# guhPLC_V0_1.net
KiCad netlist of a schematic drawn in EAGLE
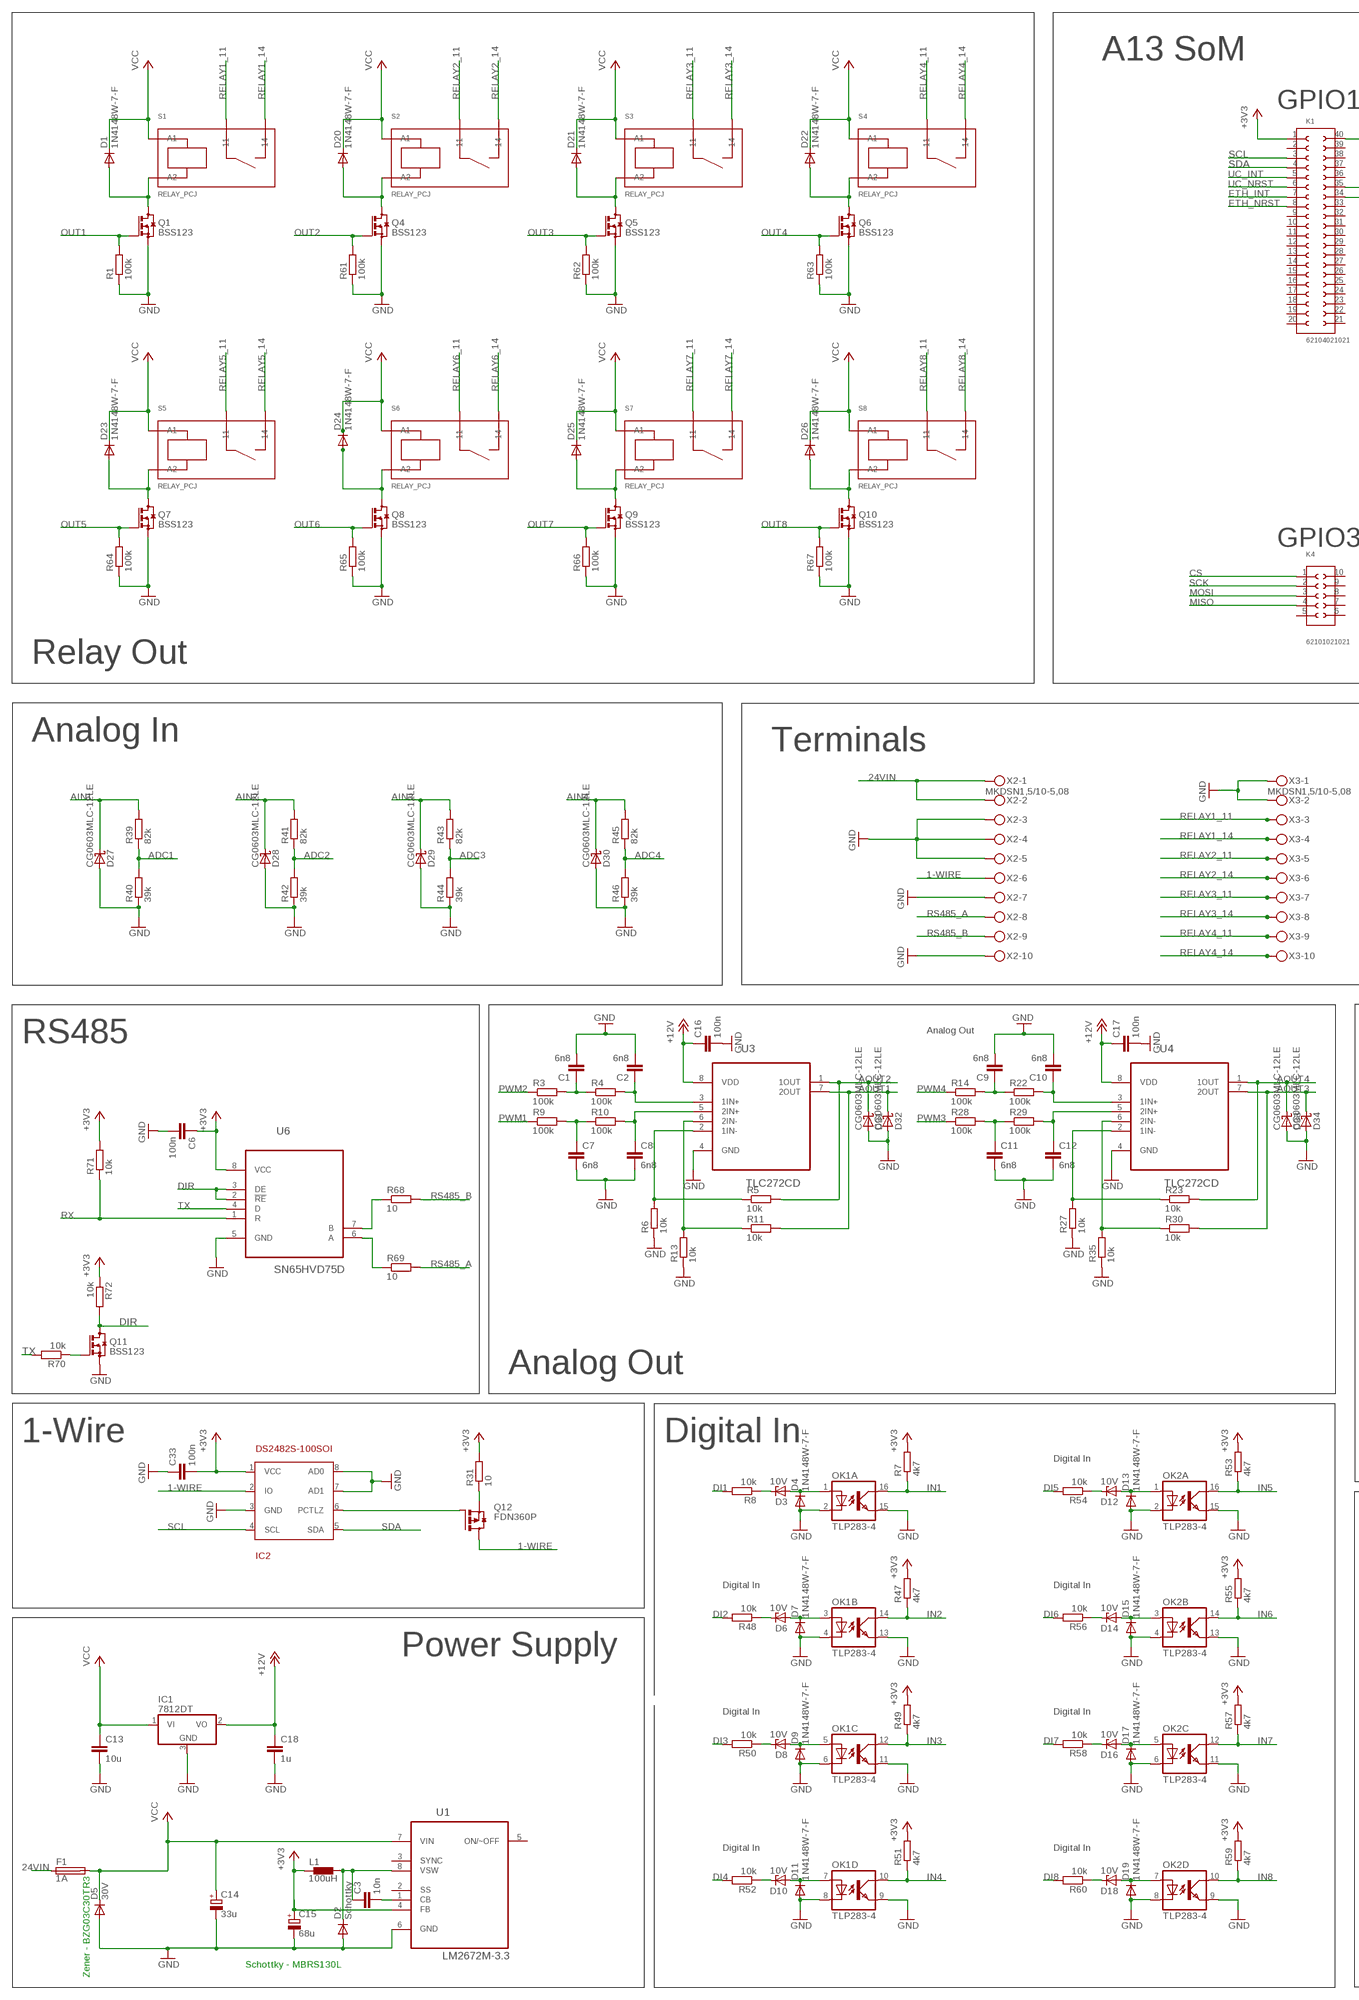
[diagram p0: schematic, sheet 1, part 1 of 2]
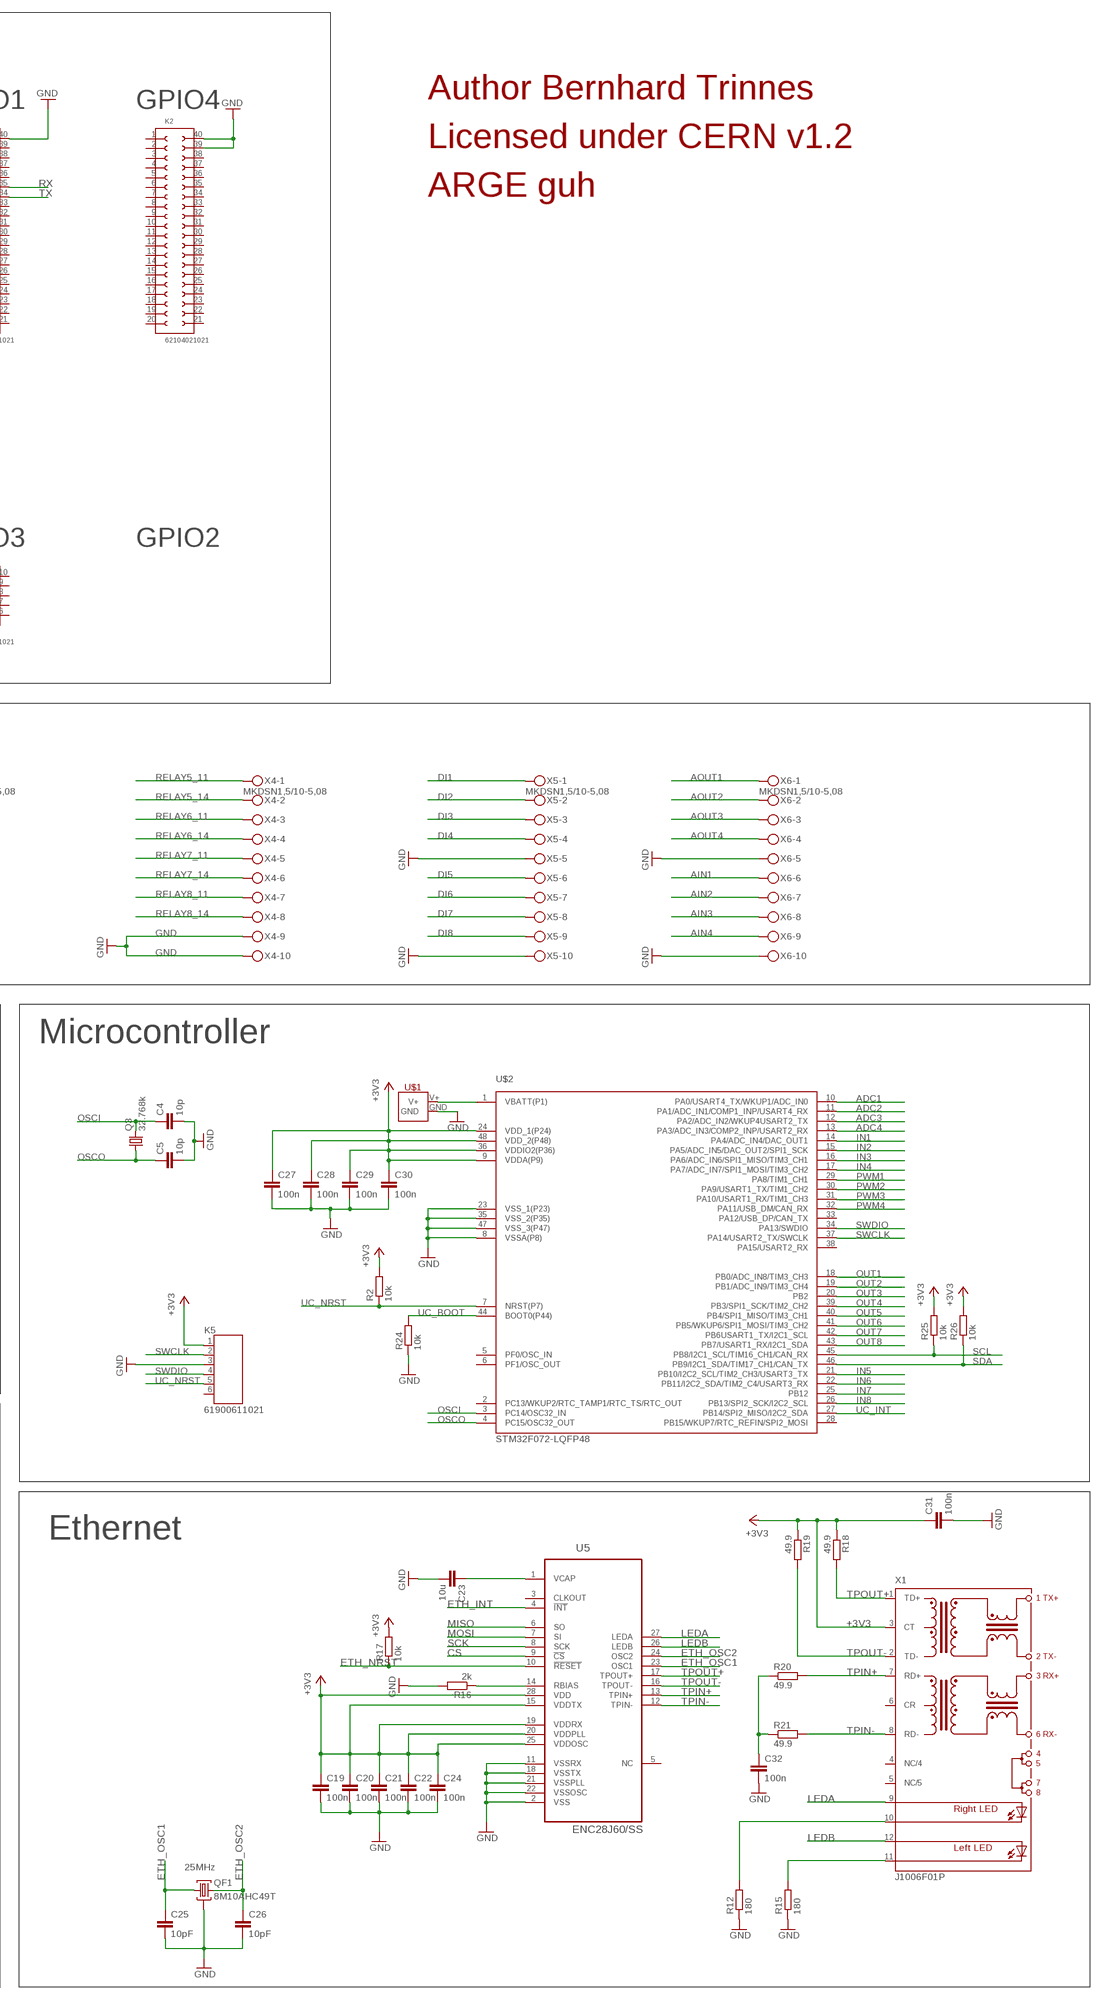
[diagram p1: schematic, sheet 1, part 2 of 2]

(export (version "E")
  (design (tool "Eeschema 10.0.6"))
  (components
    (comp (ref "C1")
      (value "6n8")
      (footprint "eagle-import:C0603")
      (libsource (lib "eagle-import") (part "C-EUC0603"))
    )
    (comp (ref "C2")
      (value "6n8")
      (footprint "eagle-import:C0603")
      (libsource (lib "eagle-import") (part "C-EUC0603"))
    )
    (comp (ref "C3")
      (value "10n")
      (footprint "eagle-import:C0603")
      (libsource (lib "eagle-import") (part "C-EUC0603"))
    )
    (comp (ref "C4")
      (value "10p")
      (footprint "eagle-import:C0603")
      (libsource (lib "eagle-import") (part "C-EUC0603"))
    )
    (comp (ref "C5")
      (value "10p")
      (footprint "eagle-import:C0603")
      (libsource (lib "eagle-import") (part "C-EUC0603"))
    )
    (comp (ref "C6")
      (value "100n")
      (footprint "eagle-import:C0504")
      (libsource (lib "eagle-import") (part "C-EUC0504"))
    )
    (comp (ref "C7")
      (value "6n8")
      (footprint "eagle-import:C0603")
      (libsource (lib "eagle-import") (part "C-EUC0603"))
    )
    (comp (ref "C8")
      (value "6n8")
      (footprint "eagle-import:C0603")
      (libsource (lib "eagle-import") (part "C-EUC0603"))
    )
    (comp (ref "C9")
      (value "6n8")
      (footprint "eagle-import:C0603")
      (libsource (lib "eagle-import") (part "C-EUC0603"))
    )
    (comp (ref "C10")
      (value "6n8")
      (footprint "eagle-import:C0603")
      (libsource (lib "eagle-import") (part "C-EUC0603"))
    )
    (comp (ref "C11")
      (value "6n8")
      (footprint "eagle-import:C0603")
      (libsource (lib "eagle-import") (part "C-EUC0603"))
    )
    (comp (ref "C12")
      (value "6n8")
      (footprint "eagle-import:C0603")
      (libsource (lib "eagle-import") (part "C-EUC0603"))
    )
    (comp (ref "C13")
      (value "10u")
      (footprint "eagle-import:C1206")
      (libsource (lib "eagle-import") (part "C-EUC1206"))
    )
    (comp (ref "C14")
      (value "33u")
      (footprint "eagle-import:CT7343")
      (libsource (lib "eagle-import") (part "CPOL-EUCT7343"))
    )
    (comp (ref "C15")
      (value "68u")
      (footprint "eagle-import:CT6032")
      (libsource (lib "eagle-import") (part "CPOL-EUCT6032"))
    )
    (comp (ref "C16")
      (value "100n")
      (footprint "eagle-import:C0603")
      (libsource (lib "eagle-import") (part "C-EUC0603"))
    )
    (comp (ref "C17")
      (value "100n")
      (footprint "eagle-import:C0603")
      (libsource (lib "eagle-import") (part "C-EUC0603"))
    )
    (comp (ref "C18")
      (value "1u")
      (footprint "eagle-import:C1206")
      (libsource (lib "eagle-import") (part "C-EUC1206"))
    )
    (comp (ref "C19")
      (value "100n")
      (footprint "eagle-import:C0603")
      (libsource (lib "eagle-import") (part "C-EUC0603"))
    )
    (comp (ref "C20")
      (value "100n")
      (footprint "eagle-import:C0603")
      (libsource (lib "eagle-import") (part "C-EUC0603"))
    )
    (comp (ref "C21")
      (value "100n")
      (footprint "eagle-import:C0603")
      (libsource (lib "eagle-import") (part "C-EUC0603"))
    )
    (comp (ref "C22")
      (value "100n")
      (footprint "eagle-import:C0603")
      (libsource (lib "eagle-import") (part "C-EUC0603"))
    )
    (comp (ref "C23")
      (value "10u")
      (footprint "eagle-import:C0603")
      (libsource (lib "eagle-import") (part "C-EUC0603"))
    )
    (comp (ref "C24")
      (value "100n")
      (footprint "eagle-import:C0603")
      (libsource (lib "eagle-import") (part "C-EUC0603"))
    )
    (comp (ref "C25")
      (value "10pF")
      (footprint "eagle-import:C0603")
      (libsource (lib "eagle-import") (part "C-EUC0603"))
    )
    (comp (ref "C26")
      (value "10pF")
      (footprint "eagle-import:C0603")
      (libsource (lib "eagle-import") (part "C-EUC0603"))
    )
    (comp (ref "C27")
      (value "100n")
      (footprint "eagle-import:C0603")
      (libsource (lib "eagle-import") (part "C-EUC0603"))
    )
    (comp (ref "C28")
      (value "100n")
      (footprint "eagle-import:C0603")
      (libsource (lib "eagle-import") (part "C-EUC0603"))
    )
    (comp (ref "C29")
      (value "100n")
      (footprint "eagle-import:C0603")
      (libsource (lib "eagle-import") (part "C-EUC0603"))
    )
    (comp (ref "C30")
      (value "100n")
      (footprint "eagle-import:C0603")
      (libsource (lib "eagle-import") (part "C-EUC0603"))
    )
    (comp (ref "C31")
      (value "100n")
      (footprint "eagle-import:C0603")
      (libsource (lib "eagle-import") (part "C-EUC0603"))
    )
    (comp (ref "C32")
      (value "100n")
      (footprint "eagle-import:C0402")
      (libsource (lib "eagle-import") (part "C-EUC0402"))
    )
    (comp (ref "C33")
      (value "100n")
      (footprint "eagle-import:C0603")
      (libsource (lib "eagle-import") (part "C-EUC0603"))
    )
    (comp (ref "D1")
      (value "1N4148W-7-F")
      (footprint "eagle-import:SOD123")
      (libsource (lib "eagle-import") (part "1N4148W-7-F"))
    )
    (comp (ref "D2")
      (value "Schottky")
      (footprint "eagle-import:DO214AA")
      (libsource (lib "eagle-import") (part "DIODE-DO214AA"))
    )
    (comp (ref "D3")
      (value "10V")
      (footprint "eagle-import:SOD80C")
      (libsource (lib "eagle-import") (part "ZENER-DIODESOD80C"))
    )
    (comp (ref "D4")
      (value "1N4148W-7-F")
      (footprint "eagle-import:SOD123")
      (libsource (lib "eagle-import") (part "1N4148W-7-F"))
    )
    (comp (ref "D5")
      (value "30V")
      (footprint "eagle-import:DO214AC")
      (libsource (lib "eagle-import") (part "DIODE-DO214AC"))
    )
    (comp (ref "D6")
      (value "10V")
      (footprint "eagle-import:SOD80C")
      (libsource (lib "eagle-import") (part "ZENER-DIODESOD80C"))
    )
    (comp (ref "D7")
      (value "1N4148W-7-F")
      (footprint "eagle-import:SOD123")
      (libsource (lib "eagle-import") (part "1N4148W-7-F"))
    )
    (comp (ref "D8")
      (value "10V")
      (footprint "eagle-import:SOD80C")
      (libsource (lib "eagle-import") (part "ZENER-DIODESOD80C"))
    )
    (comp (ref "D9")
      (value "1N4148W-7-F")
      (footprint "eagle-import:SOD123")
      (libsource (lib "eagle-import") (part "1N4148W-7-F"))
    )
    (comp (ref "D10")
      (value "10V")
      (footprint "eagle-import:SOD80C")
      (libsource (lib "eagle-import") (part "ZENER-DIODESOD80C"))
    )
    (comp (ref "D11")
      (value "1N4148W-7-F")
      (footprint "eagle-import:SOD123")
      (libsource (lib "eagle-import") (part "1N4148W-7-F"))
    )
    (comp (ref "D12")
      (value "10V")
      (footprint "eagle-import:SOD80C")
      (libsource (lib "eagle-import") (part "ZENER-DIODESOD80C"))
    )
    (comp (ref "D13")
      (value "1N4148W-7-F")
      (footprint "eagle-import:SOD123")
      (libsource (lib "eagle-import") (part "1N4148W-7-F"))
    )
    (comp (ref "D14")
      (value "10V")
      (footprint "eagle-import:SOD80C")
      (libsource (lib "eagle-import") (part "ZENER-DIODESOD80C"))
    )
    (comp (ref "D15")
      (value "1N4148W-7-F")
      (footprint "eagle-import:SOD123")
      (libsource (lib "eagle-import") (part "1N4148W-7-F"))
    )
    (comp (ref "D16")
      (value "10V")
      (footprint "eagle-import:SOD80C")
      (libsource (lib "eagle-import") (part "ZENER-DIODESOD80C"))
    )
    (comp (ref "D17")
      (value "1N4148W-7-F")
      (footprint "eagle-import:SOD123")
      (libsource (lib "eagle-import") (part "1N4148W-7-F"))
    )
    (comp (ref "D18")
      (value "10V")
      (footprint "eagle-import:SOD80C")
      (libsource (lib "eagle-import") (part "ZENER-DIODESOD80C"))
    )
    (comp (ref "D19")
      (value "1N4148W-7-F")
      (footprint "eagle-import:SOD123")
      (libsource (lib "eagle-import") (part "1N4148W-7-F"))
    )
    (comp (ref "D20")
      (value "1N4148W-7-F")
      (footprint "eagle-import:SOD123")
      (libsource (lib "eagle-import") (part "1N4148W-7-F"))
    )
    (comp (ref "D21")
      (value "1N4148W-7-F")
      (footprint "eagle-import:SOD123")
      (libsource (lib "eagle-import") (part "1N4148W-7-F"))
    )
    (comp (ref "D22")
      (value "1N4148W-7-F")
      (footprint "eagle-import:SOD123")
      (libsource (lib "eagle-import") (part "1N4148W-7-F"))
    )
    (comp (ref "D23")
      (value "1N4148W-7-F")
      (footprint "eagle-import:SOD123")
      (libsource (lib "eagle-import") (part "1N4148W-7-F"))
    )
    (comp (ref "D24")
      (value "1N4148W-7-F")
      (footprint "eagle-import:SOD123")
      (libsource (lib "eagle-import") (part "1N4148W-7-F"))
    )
    (comp (ref "D25")
      (value "1N4148W-7-F")
      (footprint "eagle-import:SOD123")
      (libsource (lib "eagle-import") (part "1N4148W-7-F"))
    )
    (comp (ref "D26")
      (value "1N4148W-7-F")
      (footprint "eagle-import:SOD123")
      (libsource (lib "eagle-import") (part "1N4148W-7-F"))
    )
    (comp (ref "D27")
      (value "CG0603MLC-12LE")
      (footprint "eagle-import:R0603")
      (libsource (lib "eagle-import") (part "CG0603MLC-12LE"))
    )
    (comp (ref "D28")
      (value "CG0603MLC-12LE")
      (footprint "eagle-import:R0603")
      (libsource (lib "eagle-import") (part "CG0603MLC-12LE"))
    )
    (comp (ref "D29")
      (value "CG0603MLC-12LE")
      (footprint "eagle-import:R0603")
      (libsource (lib "eagle-import") (part "CG0603MLC-12LE"))
    )
    (comp (ref "D30")
      (value "CG0603MLC-12LE")
      (footprint "eagle-import:R0603")
      (libsource (lib "eagle-import") (part "CG0603MLC-12LE"))
    )
    (comp (ref "D31")
      (value "CG0603MLC-12LE")
      (footprint "eagle-import:R0603")
      (libsource (lib "eagle-import") (part "CG0603MLC-12LE"))
    )
    (comp (ref "D32")
      (value "CG0603MLC-12LE")
      (footprint "eagle-import:R0603")
      (libsource (lib "eagle-import") (part "CG0603MLC-12LE"))
    )
    (comp (ref "D33")
      (value "CG0603MLC-12LE")
      (footprint "eagle-import:R0603")
      (libsource (lib "eagle-import") (part "CG0603MLC-12LE"))
    )
    (comp (ref "D34")
      (value "CG0603MLC-12LE")
      (footprint "eagle-import:R0603")
      (libsource (lib "eagle-import") (part "CG0603MLC-12LE"))
    )
    (comp (ref "F1")
      (value "1A")
      (footprint "eagle-import:LITTLEFUSE")
      (libsource (lib "eagle-import") (part "LITTLEFUSE"))
    )
    (comp (ref "IC1")
      (value "7812DT")
      (footprint "eagle-import:TO252")
      (libsource (lib "eagle-import") (part "78DT12"))
    )
    (comp (ref "IC2")
      (value "DS2482S-100SOI")
      (footprint "eagle-import:SOIC127P600X175-8N")
      (libsource (lib "eagle-import") (part "DS2482S-100SOI"))
    )
    (comp (ref "K1")
      (value "62104021021")
      (footprint "eagle-import:62104021021")
      (libsource (lib "eagle-import") (part "62104021021"))
    )
    (comp (ref "K2")
      (value "62104021021")
      (footprint "eagle-import:62104021021")
      (libsource (lib "eagle-import") (part "62104021021"))
    )
    (comp (ref "K4")
      (value "62101021021")
      (footprint "eagle-import:62101021021")
      (libsource (lib "eagle-import") (part "62101021021"))
    )
    (comp (ref "K5")
      (value "61900611021")
      (footprint "eagle-import:61900611021")
      (libsource (lib "eagle-import") (part "61900611021"))
    )
    (comp (ref "L1")
      (value "100uH")
      (footprint "eagle-import:DR1030")
      (libsource (lib "eagle-import") (part "DR1030"))
    )
    (comp (ref "OK1")
      (value "TLP283-4")
      (footprint "eagle-import:MINI-FLAT-16")
      (libsource (lib "eagle-import") (part "TLP283-4"))
    )
    (comp (ref "OK2")
      (value "TLP283-4")
      (footprint "eagle-import:MINI-FLAT-16")
      (libsource (lib "eagle-import") (part "TLP283-4"))
    )
    (comp (ref "Q1")
      (value "BSS123")
      (footprint "eagle-import:SOT23")
      (libsource (lib "eagle-import") (part "BSS123"))
    )
    (comp (ref "Q3")
      (value "32.768k")
      (footprint "eagle-import:TC26H")
      (libsource (lib "eagle-import") (part "CRYSTALTC26H"))
    )
    (comp (ref "Q4")
      (value "BSS123")
      (footprint "eagle-import:SOT23")
      (libsource (lib "eagle-import") (part "BSS123"))
    )
    (comp (ref "Q5")
      (value "BSS123")
      (footprint "eagle-import:SOT23")
      (libsource (lib "eagle-import") (part "BSS123"))
    )
    (comp (ref "Q6")
      (value "BSS123")
      (footprint "eagle-import:SOT23")
      (libsource (lib "eagle-import") (part "BSS123"))
    )
    (comp (ref "Q7")
      (value "BSS123")
      (footprint "eagle-import:SOT23")
      (libsource (lib "eagle-import") (part "BSS123"))
    )
    (comp (ref "Q8")
      (value "BSS123")
      (footprint "eagle-import:SOT23")
      (libsource (lib "eagle-import") (part "BSS123"))
    )
    (comp (ref "Q9")
      (value "BSS123")
      (footprint "eagle-import:SOT23")
      (libsource (lib "eagle-import") (part "BSS123"))
    )
    (comp (ref "Q10")
      (value "BSS123")
      (footprint "eagle-import:SOT23")
      (libsource (lib "eagle-import") (part "BSS123"))
    )
    (comp (ref "Q11")
      (value "BSS123")
      (footprint "eagle-import:SOT23")
      (libsource (lib "eagle-import") (part "BSS123"))
    )
    (comp (ref "Q12")
      (value "FDN360P")
      (footprint "eagle-import:SUPER-SOT3")
      (libsource (lib "eagle-import") (part "FDN360P"))
    )
    (comp (ref "QF1")
      (value "8M10AHC49T")
      (footprint "eagle-import:HC49U")
      (libsource (lib "eagle-import") (part "8M10AHC49T"))
    )
    (comp (ref "R1")
      (value "100k")
      (footprint "eagle-import:R0603")
      (libsource (lib "eagle-import") (part "R-EU_R0603"))
    )
    (comp (ref "R2")
      (value "10k")
      (footprint "eagle-import:R0603")
      (libsource (lib "eagle-import") (part "R-EU_R0603"))
    )
    (comp (ref "R3")
      (value "100k")
      (footprint "eagle-import:R0603")
      (libsource (lib "eagle-import") (part "R-EU_R0603"))
    )
    (comp (ref "R4")
      (value "100k")
      (footprint "eagle-import:R0603")
      (libsource (lib "eagle-import") (part "R-EU_R0603"))
    )
    (comp (ref "R5")
      (value "10k")
      (footprint "eagle-import:R0805")
      (libsource (lib "eagle-import") (part "R-EU_R0805"))
    )
    (comp (ref "R6")
      (value "10k")
      (footprint "eagle-import:R0805")
      (libsource (lib "eagle-import") (part "R-EU_R0805"))
    )
    (comp (ref "R7")
      (value "4k7")
      (footprint "eagle-import:R0603")
      (libsource (lib "eagle-import") (part "R-EU_R0603"))
    )
    (comp (ref "R8")
      (value "10k")
      (footprint "eagle-import:R0805")
      (libsource (lib "eagle-import") (part "R-EU_R0805"))
    )
    (comp (ref "R9")
      (value "100k")
      (footprint "eagle-import:R0603")
      (libsource (lib "eagle-import") (part "R-EU_R0603"))
    )
    (comp (ref "R10")
      (value "100k")
      (footprint "eagle-import:R0603")
      (libsource (lib "eagle-import") (part "R-EU_R0603"))
    )
    (comp (ref "R11")
      (value "10k")
      (footprint "eagle-import:R0805")
      (libsource (lib "eagle-import") (part "R-EU_R0805"))
    )
    (comp (ref "R12")
      (value "180")
      (footprint "eagle-import:R0603")
      (libsource (lib "eagle-import") (part "R-EU_R0603"))
    )
    (comp (ref "R13")
      (value "10k")
      (footprint "eagle-import:R0805")
      (libsource (lib "eagle-import") (part "R-EU_R0805"))
    )
    (comp (ref "R14")
      (value "100k")
      (footprint "eagle-import:R0603")
      (libsource (lib "eagle-import") (part "R-EU_R0603"))
    )
    (comp (ref "R15")
      (value "180")
      (footprint "eagle-import:R0603")
      (libsource (lib "eagle-import") (part "R-EU_R0603"))
    )
    (comp (ref "R16")
      (value "2k")
      (footprint "eagle-import:R0603")
      (libsource (lib "eagle-import") (part "R-EU_R0603"))
    )
    (comp (ref "R17")
      (value "10k")
      (footprint "eagle-import:R0603")
      (libsource (lib "eagle-import") (part "R-EU_R0603"))
    )
    (comp (ref "R18")
      (value "49.9")
      (footprint "eagle-import:R0603")
      (libsource (lib "eagle-import") (part "R-EU_R0603"))
    )
    (comp (ref "R19")
      (value "49.9")
      (footprint "eagle-import:R0603")
      (libsource (lib "eagle-import") (part "R-EU_R0603"))
    )
    (comp (ref "R20")
      (value "49.9")
      (footprint "eagle-import:R0603")
      (libsource (lib "eagle-import") (part "R-EU_R0603"))
    )
    (comp (ref "R21")
      (value "49.9")
      (footprint "eagle-import:R0603")
      (libsource (lib "eagle-import") (part "R-EU_R0603"))
    )
    (comp (ref "R22")
      (value "100k")
      (footprint "eagle-import:R0603")
      (libsource (lib "eagle-import") (part "R-EU_R0603"))
    )
    (comp (ref "R23")
      (value "10k")
      (footprint "eagle-import:R0805")
      (libsource (lib "eagle-import") (part "R-EU_R0805"))
    )
    (comp (ref "R24")
      (value "10k")
      (footprint "eagle-import:R0603")
      (libsource (lib "eagle-import") (part "R-EU_R0603"))
    )
    (comp (ref "R25")
      (value "10k")
      (footprint "eagle-import:R0603")
      (libsource (lib "eagle-import") (part "R-EU_R0603"))
    )
    (comp (ref "R26")
      (value "10k")
      (footprint "eagle-import:R0603")
      (libsource (lib "eagle-import") (part "R-EU_R0603"))
    )
    (comp (ref "R27")
      (value "10k")
      (footprint "eagle-import:R0805")
      (libsource (lib "eagle-import") (part "R-EU_R0805"))
    )
    (comp (ref "R28")
      (value "100k")
      (footprint "eagle-import:R0603")
      (libsource (lib "eagle-import") (part "R-EU_R0603"))
    )
    (comp (ref "R29")
      (value "100k")
      (footprint "eagle-import:R0603")
      (libsource (lib "eagle-import") (part "R-EU_R0603"))
    )
    (comp (ref "R30")
      (value "10k")
      (footprint "eagle-import:R0805")
      (libsource (lib "eagle-import") (part "R-EU_R0805"))
    )
    (comp (ref "R31")
      (value "10")
      (footprint "eagle-import:R0805")
      (libsource (lib "eagle-import") (part "R-EU_R0805"))
    )
    (comp (ref "R35")
      (value "10k")
      (footprint "eagle-import:R0805")
      (libsource (lib "eagle-import") (part "R-EU_R0805"))
    )
    (comp (ref "R39")
      (value "82k")
      (footprint "eagle-import:R0805")
      (libsource (lib "eagle-import") (part "R-EU_R0805"))
    )
    (comp (ref "R40")
      (value "39k")
      (footprint "eagle-import:R0805")
      (libsource (lib "eagle-import") (part "R-EU_R0805"))
    )
    (comp (ref "R41")
      (value "82k")
      (footprint "eagle-import:R0805")
      (libsource (lib "eagle-import") (part "R-EU_R0805"))
    )
    (comp (ref "R42")
      (value "39k")
      (footprint "eagle-import:R0805")
      (libsource (lib "eagle-import") (part "R-EU_R0805"))
    )
    (comp (ref "R43")
      (value "82k")
      (footprint "eagle-import:R0805")
      (libsource (lib "eagle-import") (part "R-EU_R0805"))
    )
    (comp (ref "R44")
      (value "39k")
      (footprint "eagle-import:R0805")
      (libsource (lib "eagle-import") (part "R-EU_R0805"))
    )
    (comp (ref "R45")
      (value "82k")
      (footprint "eagle-import:R0805")
      (libsource (lib "eagle-import") (part "R-EU_R0805"))
    )
    (comp (ref "R46")
      (value "39k")
      (footprint "eagle-import:R0805")
      (libsource (lib "eagle-import") (part "R-EU_R0805"))
    )
    (comp (ref "R47")
      (value "4k7")
      (footprint "eagle-import:R0603")
      (libsource (lib "eagle-import") (part "R-EU_R0603"))
    )
    (comp (ref "R48")
      (value "10k")
      (footprint "eagle-import:R0805")
      (libsource (lib "eagle-import") (part "R-EU_R0805"))
    )
    (comp (ref "R49")
      (value "4k7")
      (footprint "eagle-import:R0603")
      (libsource (lib "eagle-import") (part "R-EU_R0603"))
    )
    (comp (ref "R50")
      (value "10k")
      (footprint "eagle-import:R0805")
      (libsource (lib "eagle-import") (part "R-EU_R0805"))
    )
    (comp (ref "R51")
      (value "4k7")
      (footprint "eagle-import:R0603")
      (libsource (lib "eagle-import") (part "R-EU_R0603"))
    )
    (comp (ref "R52")
      (value "10k")
      (footprint "eagle-import:R0805")
      (libsource (lib "eagle-import") (part "R-EU_R0805"))
    )
    (comp (ref "R53")
      (value "4k7")
      (footprint "eagle-import:R0603")
      (libsource (lib "eagle-import") (part "R-EU_R0603"))
    )
    (comp (ref "R54")
      (value "10k")
      (footprint "eagle-import:R0805")
      (libsource (lib "eagle-import") (part "R-EU_R0805"))
    )
    (comp (ref "R55")
      (value "4k7")
      (footprint "eagle-import:R0603")
      (libsource (lib "eagle-import") (part "R-EU_R0603"))
    )
    (comp (ref "R56")
      (value "10k")
      (footprint "eagle-import:R0805")
      (libsource (lib "eagle-import") (part "R-EU_R0805"))
    )
    (comp (ref "R57")
      (value "4k7")
      (footprint "eagle-import:R0603")
      (libsource (lib "eagle-import") (part "R-EU_R0603"))
    )
    (comp (ref "R58")
      (value "10k")
      (footprint "eagle-import:R0805")
      (libsource (lib "eagle-import") (part "R-EU_R0805"))
    )
    (comp (ref "R59")
      (value "4k7")
      (footprint "eagle-import:R0603")
      (libsource (lib "eagle-import") (part "R-EU_R0603"))
    )
    (comp (ref "R60")
      (value "10k")
      (footprint "eagle-import:R0805")
      (libsource (lib "eagle-import") (part "R-EU_R0805"))
    )
    (comp (ref "R61")
      (value "100k")
      (footprint "eagle-import:R0603")
      (libsource (lib "eagle-import") (part "R-EU_R0603"))
    )
    (comp (ref "R62")
      (value "100k")
      (footprint "eagle-import:R0603")
      (libsource (lib "eagle-import") (part "R-EU_R0603"))
    )
    (comp (ref "R63")
      (value "100k")
      (footprint "eagle-import:R0603")
      (libsource (lib "eagle-import") (part "R-EU_R0603"))
    )
    (comp (ref "R64")
      (value "100k")
      (footprint "eagle-import:R0603")
      (libsource (lib "eagle-import") (part "R-EU_R0603"))
    )
    (comp (ref "R65")
      (value "100k")
      (footprint "eagle-import:R0603")
      (libsource (lib "eagle-import") (part "R-EU_R0603"))
    )
    (comp (ref "R66")
      (value "100k")
      (footprint "eagle-import:R0603")
      (libsource (lib "eagle-import") (part "R-EU_R0603"))
    )
    (comp (ref "R67")
      (value "100k")
      (footprint "eagle-import:R0603")
      (libsource (lib "eagle-import") (part "R-EU_R0603"))
    )
    (comp (ref "R68")
      (value "10")
      (footprint "eagle-import:R0603")
      (libsource (lib "eagle-import") (part "R-EU_R0603"))
    )
    (comp (ref "R69")
      (value "10")
      (footprint "eagle-import:R0603")
      (libsource (lib "eagle-import") (part "R-EU_R0603"))
    )
    (comp (ref "R70")
      (value "10k")
      (footprint "eagle-import:R0603")
      (libsource (lib "eagle-import") (part "R-EU_R0603"))
    )
    (comp (ref "R71")
      (value "10k")
      (footprint "eagle-import:R0603")
      (libsource (lib "eagle-import") (part "R-EU_R0603"))
    )
    (comp (ref "R72")
      (value "10k")
      (footprint "eagle-import:R0603")
      (libsource (lib "eagle-import") (part "R-EU_R0603"))
    )
    (comp (ref "S1")
      (value "RELAY_PCJ")
      (footprint "eagle-import:RELAY_PCJ")
      (libsource (lib "eagle-import") (part "RELAY_PCJ"))
    )
    (comp (ref "S2")
      (value "RELAY_PCJ")
      (footprint "eagle-import:RELAY_PCJ")
      (libsource (lib "eagle-import") (part "RELAY_PCJ"))
    )
    (comp (ref "S3")
      (value "RELAY_PCJ")
      (footprint "eagle-import:RELAY_PCJ")
      (libsource (lib "eagle-import") (part "RELAY_PCJ"))
    )
    (comp (ref "S4")
      (value "RELAY_PCJ")
      (footprint "eagle-import:RELAY_PCJ")
      (libsource (lib "eagle-import") (part "RELAY_PCJ"))
    )
    (comp (ref "S5")
      (value "RELAY_PCJ")
      (footprint "eagle-import:RELAY_PCJ")
      (libsource (lib "eagle-import") (part "RELAY_PCJ"))
    )
    (comp (ref "S6")
      (value "RELAY_PCJ")
      (footprint "eagle-import:RELAY_PCJ")
      (libsource (lib "eagle-import") (part "RELAY_PCJ"))
    )
    (comp (ref "S7")
      (value "RELAY_PCJ")
      (footprint "eagle-import:RELAY_PCJ")
      (libsource (lib "eagle-import") (part "RELAY_PCJ"))
    )
    (comp (ref "S8")
      (value "RELAY_PCJ")
      (footprint "eagle-import:RELAY_PCJ")
      (libsource (lib "eagle-import") (part "RELAY_PCJ"))
    )
    (comp (ref "U$1")
      (value "MULTICOMP-CH7410-2032LF")
      (footprint "eagle-import:MULTICOMP-CH7410-2032LF")
      (libsource (lib "eagle-import") (part "MULTICOMP-CH7410-2032LF"))
    )
    (comp (ref "U$2")
      (value "STM32F072-LQFP48")
      (footprint "eagle-import:LQFP48")
      (libsource (lib "eagle-import") (part "STM32F072-LQFP48"))
    )
    (comp (ref "U1")
      (value "LM2672M-3.3")
      (footprint "eagle-import:SOIC127P600X175-8N")
      (libsource (lib "eagle-import") (part "LM2672M-3.3"))
    )
    (comp (ref "U3")
      (value "TLC272CD")
      (footprint "eagle-import:SOIC127P600X175-8N")
      (libsource (lib "eagle-import") (part "TLC272CD"))
    )
    (comp (ref "U4")
      (value "TLC272CD")
      (footprint "eagle-import:SOIC127P600X175-8N")
      (libsource (lib "eagle-import") (part "TLC272CD"))
    )
    (comp (ref "U5")
      (value "ENC28J60/SS")
      (footprint "eagle-import:SOP65P780X200-28N")
      (libsource (lib "eagle-import") (part "ENC28J60/SS"))
    )
    (comp (ref "U6")
      (value "SN65HVD75D")
      (footprint "eagle-import:SOIC127P600X175-8N")
      (libsource (lib "eagle-import") (part "SN65HVD75D"))
    )
    (comp (ref "X1")
      (value "J1006F01P")
      (footprint "eagle-import:J1")
      (libsource (lib "eagle-import") (part "J1006F01P"))
    )
    (comp (ref "X2")
      (value "MKDSN1,5/10-5,08")
      (footprint "eagle-import:MKDSN1,5_10-5,08")
      (fields (field (name "MPN") "SMKDSN1,5/10-5,08"))
      (libsource (lib "eagle-import") (part "MKDSN1,5/10-5,08"))
    )
    (comp (ref "X3")
      (value "MKDSN1,5/10-5,08")
      (footprint "eagle-import:MKDSN1,5_10-5,08")
      (fields (field (name "MPN") "SMKDSN1,5/10-5,08"))
      (libsource (lib "eagle-import") (part "MKDSN1,5/10-5,08"))
    )
    (comp (ref "X4")
      (value "MKDSN1,5/10-5,08")
      (footprint "eagle-import:MKDSN1,5_10-5,08")
      (fields (field (name "MPN") "SMKDSN1,5/10-5,08"))
      (libsource (lib "eagle-import") (part "MKDSN1,5/10-5,08"))
    )
    (comp (ref "X5")
      (value "MKDSN1,5/10-5,08")
      (footprint "eagle-import:MKDSN1,5_10-5,08")
      (fields (field (name "MPN") "SMKDSN1,5/10-5,08"))
      (libsource (lib "eagle-import") (part "MKDSN1,5/10-5,08"))
    )
    (comp (ref "X6")
      (value "MKDSN1,5/10-5,08")
      (footprint "eagle-import:MKDSN1,5_10-5,08")
      (fields (field (name "MPN") "SMKDSN1,5/10-5,08"))
      (libsource (lib "eagle-import") (part "MKDSN1,5/10-5,08"))
    )
  )
  (nets
    (net (code "1") (name "+3V3") (class "Default")
      (node (ref "C15") (pin "+") (pinfunction "+_+") (pintype "passive"))
      (node (ref "C19") (pin "1") (pinfunction "1_1") (pintype "passive"))
      (node (ref "C20") (pin "1") (pinfunction "1_1") (pintype "passive"))
      (node (ref "C21") (pin "1") (pinfunction "1_1") (pintype "passive"))
      (node (ref "C22") (pin "1") (pinfunction "1_1") (pintype "passive"))
      (node (ref "C24") (pin "1") (pinfunction "1_1") (pintype "passive"))
      (node (ref "C27") (pin "1") (pinfunction "1_1") (pintype "passive"))
      (node (ref "C28") (pin "1") (pinfunction "1_1") (pintype "passive"))
      (node (ref "C29") (pin "1") (pinfunction "1_1") (pintype "passive"))
      (node (ref "C30") (pin "1") (pinfunction "1_1") (pintype "passive"))
      (node (ref "C31") (pin "1") (pinfunction "1_1") (pintype "passive"))
      (node (ref "C33") (pin "2") (pinfunction "2_2") (pintype "passive"))
      (node (ref "C6") (pin "1") (pinfunction "1_1") (pintype "passive"))
      (node (ref "IC2") (pin "1") (pinfunction "VCC_1") (pintype "power_in"))
      (node (ref "K1") (pin "1") (pinfunction "1_1") (pintype "passive"))
      (node (ref "K5") (pin "1") (pinfunction "1_1") (pintype "passive"))
      (node (ref "L1") (pin "1") (pinfunction "1_1") (pintype "passive"))
      (node (ref "R17") (pin "2") (pinfunction "2_2") (pintype "passive"))
      (node (ref "R18") (pin "1") (pinfunction "1_1") (pintype "passive"))
      (node (ref "R19") (pin "1") (pinfunction "1_1") (pintype "passive"))
      (node (ref "R2") (pin "2") (pinfunction "2_2") (pintype "passive"))
      (node (ref "R25") (pin "2") (pinfunction "2_2") (pintype "passive"))
      (node (ref "R26") (pin "2") (pinfunction "2_2") (pintype "passive"))
      (node (ref "R31") (pin "2") (pinfunction "2_2") (pintype "passive"))
      (node (ref "R47") (pin "2") (pinfunction "2_2") (pintype "passive"))
      (node (ref "R49") (pin "2") (pinfunction "2_2") (pintype "passive"))
      (node (ref "R51") (pin "2") (pinfunction "2_2") (pintype "passive"))
      (node (ref "R53") (pin "2") (pinfunction "2_2") (pintype "passive"))
      (node (ref "R55") (pin "2") (pinfunction "2_2") (pintype "passive"))
      (node (ref "R57") (pin "2") (pinfunction "2_2") (pintype "passive"))
      (node (ref "R59") (pin "2") (pinfunction "2_2") (pintype "passive"))
      (node (ref "R7") (pin "2") (pinfunction "2_2") (pintype "passive"))
      (node (ref "R71") (pin "2") (pinfunction "2_2") (pintype "passive"))
      (node (ref "R72") (pin "1") (pinfunction "1_1") (pintype "passive"))
      (node (ref "U$2") (pin "24") (pinfunction "VDD_1(P24)_24") (pintype "bidirectional"))
      (node (ref "U$2") (pin "36") (pinfunction "VDDIO2(P36)_36") (pintype "bidirectional"))
      (node (ref "U$2") (pin "48") (pinfunction "VDD_2(P48)_48") (pintype "bidirectional"))
      (node (ref "U$2") (pin "9") (pinfunction "VDDA(P9)_9") (pintype "bidirectional"))
      (node (ref "U1") (pin "4") (pinfunction "FB_4") (pintype "input"))
      (node (ref "U5") (pin "15") (pinfunction "VDDTX_15") (pintype "power_in"))
      (node (ref "U5") (pin "19") (pinfunction "VDDRX_19") (pintype "power_in"))
      (node (ref "U5") (pin "20") (pinfunction "VDDPLL_20") (pintype "power_in"))
      (node (ref "U5") (pin "25") (pinfunction "VDDOSC_25") (pintype "power_in"))
      (node (ref "U5") (pin "28") (pinfunction "VDD_28") (pintype "power_in"))
      (node (ref "U6") (pin "8") (pinfunction "VCC_8") (pintype "power_in"))
      (node (ref "X1") (pin "3") (pinfunction "CT_3") (pintype "input"))
    )
    (net (code "2") (name "+12V") (class "Default")
      (node (ref "C16") (pin "1") (pinfunction "1_1") (pintype "passive"))
      (node (ref "C17") (pin "1") (pinfunction "1_1") (pintype "passive"))
      (node (ref "C18") (pin "1") (pinfunction "1_1") (pintype "passive"))
      (node (ref "IC1") (pin "2") (pinfunction "VO_2") (pintype "passive"))
      (node (ref "U3") (pin "8") (pinfunction "VDD_8") (pintype "power_in"))
      (node (ref "U4") (pin "8") (pinfunction "VDD_8") (pintype "power_in"))
    )
    (net (code "3") (name "/1-WIRE") (class "Default")
      (node (ref "IC2") (pin "2") (pinfunction "IO_2") (pintype "bidirectional"))
      (node (ref "Q12") (pin "3") (pinfunction "D_3") (pintype "passive"))
      (node (ref "X2") (pin "6") (pinfunction "KL_6") (pintype "passive"))
    )
    (net (code "4") (name "/24VIN") (class "Default")
      (node (ref "F1") (pin "1") (pinfunction "1_1") (pintype "passive"))
      (node (ref "X2") (pin "1") (pinfunction "KL_1") (pintype "passive"))
      (node (ref "X2") (pin "2") (pinfunction "KL_2") (pintype "passive"))
    )
    (net (code "5") (name "/ADC1") (class "Default")
      (node (ref "R39") (pin "1") (pinfunction "1_1") (pintype "passive"))
      (node (ref "R40") (pin "2") (pinfunction "2_2") (pintype "passive"))
      (node (ref "U$2") (pin "10") (pinfunction "PA0/USART4_TX/WKUP1/ADC_IN0_10") (pintype "bidirectional"))
    )
    (net (code "6") (name "/ADC2") (class "Default")
      (node (ref "R41") (pin "1") (pinfunction "1_1") (pintype "passive"))
      (node (ref "R42") (pin "2") (pinfunction "2_2") (pintype "passive"))
      (node (ref "U$2") (pin "11") (pinfunction "PA1/ADC_IN1/COMP1_INP/USART4_RX_11") (pintype "bidirectional"))
    )
    (net (code "7") (name "/ADC3") (class "Default")
      (node (ref "R43") (pin "1") (pinfunction "1_1") (pintype "passive"))
      (node (ref "R44") (pin "2") (pinfunction "2_2") (pintype "passive"))
      (node (ref "U$2") (pin "12") (pinfunction "PA2/ADC_IN2/WKUP4USART2_TX_12") (pintype "bidirectional"))
    )
    (net (code "8") (name "/ADC4") (class "Default")
      (node (ref "R45") (pin "1") (pinfunction "1_1") (pintype "passive"))
      (node (ref "R46") (pin "2") (pinfunction "2_2") (pintype "passive"))
      (node (ref "U$2") (pin "13") (pinfunction "PA3/ADC_IN3/COMP2_INP/USART2_RX_13") (pintype "bidirectional"))
    )
    (net (code "9") (name "/AIN1") (class "Default")
      (node (ref "D27") (pin "2") (pinfunction "C_2") (pintype "passive"))
      (node (ref "R39") (pin "2") (pinfunction "2_2") (pintype "passive"))
      (node (ref "X6") (pin "6") (pinfunction "KL_6") (pintype "passive"))
    )
    (net (code "10") (name "/AIN2") (class "Default")
      (node (ref "D28") (pin "2") (pinfunction "C_2") (pintype "passive"))
      (node (ref "R41") (pin "2") (pinfunction "2_2") (pintype "passive"))
      (node (ref "X6") (pin "7") (pinfunction "KL_7") (pintype "passive"))
    )
    (net (code "11") (name "/AIN3") (class "Default")
      (node (ref "D29") (pin "2") (pinfunction "C_2") (pintype "passive"))
      (node (ref "R43") (pin "2") (pinfunction "2_2") (pintype "passive"))
      (node (ref "X6") (pin "8") (pinfunction "KL_8") (pintype "passive"))
    )
    (net (code "12") (name "/AIN4") (class "Default")
      (node (ref "D30") (pin "2") (pinfunction "C_2") (pintype "passive"))
      (node (ref "R45") (pin "2") (pinfunction "2_2") (pintype "passive"))
      (node (ref "X6") (pin "9") (pinfunction "KL_9") (pintype "passive"))
    )
    (net (code "13") (name "/AOUT1") (class "Default")
      (node (ref "D32") (pin "2") (pinfunction "C_2") (pintype "passive"))
      (node (ref "R11") (pin "2") (pinfunction "2_2") (pintype "passive"))
      (node (ref "U3") (pin "7") (pinfunction "2OUT_7") (pintype "output"))
      (node (ref "X6") (pin "1") (pinfunction "KL_1") (pintype "passive"))
    )
    (net (code "14") (name "/AOUT2") (class "Default")
      (node (ref "D31") (pin "2") (pinfunction "C_2") (pintype "passive"))
      (node (ref "R5") (pin "2") (pinfunction "2_2") (pintype "passive"))
      (node (ref "U3") (pin "1") (pinfunction "1OUT_1") (pintype "output"))
      (node (ref "X6") (pin "2") (pinfunction "KL_2") (pintype "passive"))
    )
    (net (code "15") (name "/AOUT3") (class "Default")
      (node (ref "D34") (pin "2") (pinfunction "C_2") (pintype "passive"))
      (node (ref "R30") (pin "2") (pinfunction "2_2") (pintype "passive"))
      (node (ref "U4") (pin "7") (pinfunction "2OUT_7") (pintype "output"))
      (node (ref "X6") (pin "3") (pinfunction "KL_3") (pintype "passive"))
    )
    (net (code "16") (name "/AOUT4") (class "Default")
      (node (ref "D33") (pin "2") (pinfunction "C_2") (pintype "passive"))
      (node (ref "R23") (pin "2") (pinfunction "2_2") (pintype "passive"))
      (node (ref "U4") (pin "1") (pinfunction "1OUT_1") (pintype "output"))
      (node (ref "X6") (pin "4") (pinfunction "KL_4") (pintype "passive"))
    )
    (net (code "17") (name "/CS") (class "Default")
      (node (ref "K4") (pin "1") (pinfunction "1_1") (pintype "passive"))
      (node (ref "U5") (pin "9") (pinfunction "~{CS}_9") (pintype "passive"))
    )
    (net (code "18") (name "/DI1") (class "Default")
      (node (ref "R8") (pin "2") (pinfunction "2_2") (pintype "passive"))
      (node (ref "X5") (pin "1") (pinfunction "KL_1") (pintype "passive"))
    )
    (net (code "19") (name "/DI2") (class "Default")
      (node (ref "R48") (pin "2") (pinfunction "2_2") (pintype "passive"))
      (node (ref "X5") (pin "2") (pinfunction "KL_2") (pintype "passive"))
    )
    (net (code "20") (name "/DI3") (class "Default")
      (node (ref "R50") (pin "2") (pinfunction "2_2") (pintype "passive"))
      (node (ref "X5") (pin "3") (pinfunction "KL_3") (pintype "passive"))
    )
    (net (code "21") (name "/DI4") (class "Default")
      (node (ref "R52") (pin "2") (pinfunction "2_2") (pintype "passive"))
      (node (ref "X5") (pin "4") (pinfunction "KL_4") (pintype "passive"))
    )
    (net (code "22") (name "/DI5") (class "Default")
      (node (ref "R54") (pin "2") (pinfunction "2_2") (pintype "passive"))
      (node (ref "X5") (pin "6") (pinfunction "KL_6") (pintype "passive"))
    )
    (net (code "23") (name "/DI6") (class "Default")
      (node (ref "R56") (pin "2") (pinfunction "2_2") (pintype "passive"))
      (node (ref "X5") (pin "7") (pinfunction "KL_7") (pintype "passive"))
    )
    (net (code "24") (name "/DI7") (class "Default")
      (node (ref "R58") (pin "2") (pinfunction "2_2") (pintype "passive"))
      (node (ref "X5") (pin "8") (pinfunction "KL_8") (pintype "passive"))
    )
    (net (code "25") (name "/DI8") (class "Default")
      (node (ref "R60") (pin "2") (pinfunction "2_2") (pintype "passive"))
      (node (ref "X5") (pin "9") (pinfunction "KL_9") (pintype "passive"))
    )
    (net (code "26") (name "/DIR") (class "Default")
      (node (ref "Q11") (pin "3") (pinfunction "D_3") (pintype "passive"))
      (node (ref "R72") (pin "2") (pinfunction "2_2") (pintype "passive"))
      (node (ref "U6") (pin "2") (pinfunction "~{RE}_2") (pintype "input"))
      (node (ref "U6") (pin "3") (pinfunction "DE_3") (pintype "input"))
    )
    (net (code "27") (name "/ETH_INT") (class "Default")
      (node (ref "K1") (pin "7") (pinfunction "7_7") (pintype "passive"))
      (node (ref "U5") (pin "4") (pinfunction "~{INT}_4") (pintype "passive"))
    )
    (net (code "28") (name "/ETH_NRST") (class "Default")
      (node (ref "K1") (pin "8") (pinfunction "8_8") (pintype "passive"))
      (node (ref "R17") (pin "1") (pinfunction "1_1") (pintype "passive"))
      (node (ref "U5") (pin "10") (pinfunction "~{RESET}_10") (pintype "passive"))
    )
    (net (code "29") (name "/ETH_OSC1") (class "Default")
      (node (ref "C25") (pin "1") (pinfunction "1_1") (pintype "passive"))
      (node (ref "QF1") (pin "1") (pinfunction "1_1") (pintype "passive"))
      (node (ref "U5") (pin "23") (pinfunction "OSC1_23") (pintype "passive"))
    )
    (net (code "30") (name "/ETH_OSC2") (class "Default")
      (node (ref "C26") (pin "1") (pinfunction "1_1") (pintype "passive"))
      (node (ref "QF1") (pin "3") (pinfunction "3_3") (pintype "passive"))
      (node (ref "U5") (pin "24") (pinfunction "OSC2_24") (pintype "passive"))
    )
    (net (code "31") (name "/IN1") (class "Default")
      (node (ref "OK1") (pin "16") (pinfunction "COL_16") (pintype "passive"))
      (node (ref "R7") (pin "1") (pinfunction "1_1") (pintype "passive"))
      (node (ref "U$2") (pin "14") (pinfunction "PA4/ADC_IN4/DAC_OUT1_14") (pintype "bidirectional"))
    )
    (net (code "32") (name "/IN2") (class "Default")
      (node (ref "OK1") (pin "14") (pinfunction "COL_14") (pintype "passive"))
      (node (ref "R47") (pin "1") (pinfunction "1_1") (pintype "passive"))
      (node (ref "U$2") (pin "15") (pinfunction "PA5/ADC_IN5/DAC_OUT2/SPI1_SCK_15") (pintype "bidirectional"))
    )
    (net (code "33") (name "/IN3") (class "Default")
      (node (ref "OK1") (pin "12") (pinfunction "COL_12") (pintype "passive"))
      (node (ref "R49") (pin "1") (pinfunction "1_1") (pintype "passive"))
      (node (ref "U$2") (pin "16") (pinfunction "PA6/ADC_IN6/SPI1_MISO/TIM3_CH1_16") (pintype "bidirectional"))
    )
    (net (code "34") (name "/IN4") (class "Default")
      (node (ref "OK1") (pin "10") (pinfunction "COL_10") (pintype "passive"))
      (node (ref "R51") (pin "1") (pinfunction "1_1") (pintype "passive"))
      (node (ref "U$2") (pin "17") (pinfunction "PA7/ADC_IN7/SPI1_MOSI/TIM3_CH2_17") (pintype "bidirectional"))
    )
    (net (code "35") (name "/IN5") (class "Default")
      (node (ref "OK2") (pin "16") (pinfunction "COL_16") (pintype "passive"))
      (node (ref "R53") (pin "1") (pinfunction "1_1") (pintype "passive"))
      (node (ref "U$2") (pin "21") (pinfunction "PB10/I2C2_SCL/TIM2_CH3/USART3_TX_21") (pintype "bidirectional"))
    )
    (net (code "36") (name "/IN6") (class "Default")
      (node (ref "OK2") (pin "14") (pinfunction "COL_14") (pintype "passive"))
      (node (ref "R55") (pin "1") (pinfunction "1_1") (pintype "passive"))
      (node (ref "U$2") (pin "22") (pinfunction "PB11/I2C2_SDA/TIM2_C4/USART3_RX_22") (pintype "bidirectional"))
    )
    (net (code "37") (name "/IN7") (class "Default")
      (node (ref "OK2") (pin "12") (pinfunction "COL_12") (pintype "passive"))
      (node (ref "R57") (pin "1") (pinfunction "1_1") (pintype "passive"))
      (node (ref "U$2") (pin "25") (pinfunction "PB12_25") (pintype "bidirectional"))
    )
    (net (code "38") (name "/IN8") (class "Default")
      (node (ref "OK2") (pin "10") (pinfunction "COL_10") (pintype "passive"))
      (node (ref "R59") (pin "1") (pinfunction "1_1") (pintype "passive"))
      (node (ref "U$2") (pin "26") (pinfunction "PB13/SPI2_SCK/I2C2_SCL_26") (pintype "bidirectional"))
    )
    (net (code "39") (name "/LEDA") (class "Default")
      (node (ref "U5") (pin "27") (pinfunction "LEDA_27") (pintype "passive"))
      (node (ref "X1") (pin "9") (pinfunction "A-R_9") (pintype "passive"))
    )
    (net (code "40") (name "/LEDB") (class "Default")
      (node (ref "U5") (pin "26") (pinfunction "LEDB_26") (pintype "passive"))
      (node (ref "X1") (pin "12") (pinfunction "A-L_12") (pintype "passive"))
    )
    (net (code "41") (name "/MISO") (class "Default")
      (node (ref "K4") (pin "4") (pinfunction "4_4") (pintype "passive"))
      (node (ref "U5") (pin "6") (pinfunction "SO_6") (pintype "passive"))
    )
    (net (code "42") (name "/MOSI") (class "Default")
      (node (ref "K4") (pin "3") (pinfunction "3_3") (pintype "passive"))
      (node (ref "U5") (pin "7") (pinfunction "SI_7") (pintype "passive"))
    )
    (net (code "43") (name "/OSCI") (class "Default")
      (node (ref "C4") (pin "1") (pinfunction "1_1") (pintype "passive"))
      (node (ref "Q3") (pin "2") (pinfunction "2_2") (pintype "passive"))
      (node (ref "U$2") (pin "3") (pinfunction "PC14/OSC32_IN_3") (pintype "bidirectional"))
    )
    (net (code "44") (name "/OSCO") (class "Default")
      (node (ref "C5") (pin "1") (pinfunction "1_1") (pintype "passive"))
      (node (ref "Q3") (pin "1") (pinfunction "1_1") (pintype "passive"))
      (node (ref "U$2") (pin "4") (pinfunction "PC15/OSC32_OUT_4") (pintype "bidirectional"))
    )
    (net (code "45") (name "/OUT1") (class "Default")
      (node (ref "Q1") (pin "1") (pinfunction "G_1") (pintype "passive"))
      (node (ref "R1") (pin "2") (pinfunction "2_2") (pintype "passive"))
      (node (ref "U$2") (pin "18") (pinfunction "PB0/ADC_IN8/TIM3_CH3_18") (pintype "bidirectional"))
    )
    (net (code "46") (name "/OUT2") (class "Default")
      (node (ref "Q4") (pin "1") (pinfunction "G_1") (pintype "passive"))
      (node (ref "R61") (pin "2") (pinfunction "2_2") (pintype "passive"))
      (node (ref "U$2") (pin "19") (pinfunction "PB1/ADC_IN9/TIM3_CH4_19") (pintype "bidirectional"))
    )
    (net (code "47") (name "/OUT3") (class "Default")
      (node (ref "Q5") (pin "1") (pinfunction "G_1") (pintype "passive"))
      (node (ref "R62") (pin "2") (pinfunction "2_2") (pintype "passive"))
      (node (ref "U$2") (pin "20") (pinfunction "PB2_20") (pintype "bidirectional"))
    )
    (net (code "48") (name "/OUT4") (class "Default")
      (node (ref "Q6") (pin "1") (pinfunction "G_1") (pintype "passive"))
      (node (ref "R63") (pin "2") (pinfunction "2_2") (pintype "passive"))
      (node (ref "U$2") (pin "39") (pinfunction "PB3/SPI1_SCK/TIM2_CH2_39") (pintype "bidirectional"))
    )
    (net (code "49") (name "/OUT5") (class "Default")
      (node (ref "Q7") (pin "1") (pinfunction "G_1") (pintype "passive"))
      (node (ref "R64") (pin "2") (pinfunction "2_2") (pintype "passive"))
      (node (ref "U$2") (pin "40") (pinfunction "PB4/SPI1_MISO/TIM3_CH1_40") (pintype "bidirectional"))
    )
    (net (code "50") (name "/OUT6") (class "Default")
      (node (ref "Q8") (pin "1") (pinfunction "G_1") (pintype "passive"))
      (node (ref "R65") (pin "2") (pinfunction "2_2") (pintype "passive"))
      (node (ref "U$2") (pin "41") (pinfunction "PB5/WKUP6/SPI1_MOSI/TIM3_CH2_41") (pintype "bidirectional"))
    )
    (net (code "51") (name "/OUT7") (class "Default")
      (node (ref "Q9") (pin "1") (pinfunction "G_1") (pintype "passive"))
      (node (ref "R66") (pin "2") (pinfunction "2_2") (pintype "passive"))
      (node (ref "U$2") (pin "42") (pinfunction "PB6USART1_TX/I2C1_SCL_42") (pintype "bidirectional"))
    )
    (net (code "52") (name "/OUT8") (class "Default")
      (node (ref "Q10") (pin "1") (pinfunction "G_1") (pintype "passive"))
      (node (ref "R67") (pin "2") (pinfunction "2_2") (pintype "passive"))
      (node (ref "U$2") (pin "43") (pinfunction "PB7/USART1_RX/I2C1_SDA_43") (pintype "bidirectional"))
    )
    (net (code "53") (name "/PWM1") (class "Default")
      (node (ref "R9") (pin "1") (pinfunction "1_1") (pintype "passive"))
      (node (ref "U$2") (pin "29") (pinfunction "PA8/TIM1_CH1_29") (pintype "bidirectional"))
    )
    (net (code "54") (name "/PWM2") (class "Default")
      (node (ref "R3") (pin "1") (pinfunction "1_1") (pintype "passive"))
      (node (ref "U$2") (pin "30") (pinfunction "PA9/USART1_TX/TIM1_CH2_30") (pintype "bidirectional"))
    )
    (net (code "55") (name "/PWM3") (class "Default")
      (node (ref "R28") (pin "1") (pinfunction "1_1") (pintype "passive"))
      (node (ref "U$2") (pin "31") (pinfunction "PA10/USART1_RX/TIM1_CH3_31") (pintype "bidirectional"))
    )
    (net (code "56") (name "/PWM4") (class "Default")
      (node (ref "R14") (pin "1") (pinfunction "1_1") (pintype "passive"))
      (node (ref "U$2") (pin "32") (pinfunction "PA11/USB_DM/CAN_RX_32") (pintype "bidirectional"))
    )
    (net (code "57") (name "/RELAY1_11") (class "Default")
      (node (ref "S1") (pin "11") (pinfunction "11_11") (pintype "bidirectional"))
      (node (ref "X3") (pin "3") (pinfunction "KL_3") (pintype "passive"))
    )
    (net (code "58") (name "/RELAY1_14") (class "Default")
      (node (ref "S1") (pin "14") (pinfunction "14_14") (pintype "bidirectional"))
      (node (ref "X3") (pin "4") (pinfunction "KL_4") (pintype "passive"))
    )
    (net (code "59") (name "/RELAY2_11") (class "Default")
      (node (ref "S2") (pin "11") (pinfunction "11_11") (pintype "bidirectional"))
      (node (ref "X3") (pin "5") (pinfunction "KL_5") (pintype "passive"))
    )
    (net (code "60") (name "/RELAY2_14") (class "Default")
      (node (ref "S2") (pin "14") (pinfunction "14_14") (pintype "bidirectional"))
      (node (ref "X3") (pin "6") (pinfunction "KL_6") (pintype "passive"))
    )
    (net (code "61") (name "/RELAY3_11") (class "Default")
      (node (ref "S3") (pin "11") (pinfunction "11_11") (pintype "bidirectional"))
      (node (ref "X3") (pin "7") (pinfunction "KL_7") (pintype "passive"))
    )
    (net (code "62") (name "/RELAY3_14") (class "Default")
      (node (ref "S3") (pin "14") (pinfunction "14_14") (pintype "bidirectional"))
      (node (ref "X3") (pin "8") (pinfunction "KL_8") (pintype "passive"))
    )
    (net (code "63") (name "/RELAY4_11") (class "Default")
      (node (ref "S4") (pin "11") (pinfunction "11_11") (pintype "bidirectional"))
      (node (ref "X3") (pin "9") (pinfunction "KL_9") (pintype "passive"))
    )
    (net (code "64") (name "/RELAY4_14") (class "Default")
      (node (ref "S4") (pin "14") (pinfunction "14_14") (pintype "bidirectional"))
      (node (ref "X3") (pin "10") (pinfunction "KL_10") (pintype "passive"))
    )
    (net (code "65") (name "/RELAY5_11") (class "Default")
      (node (ref "S5") (pin "11") (pinfunction "11_11") (pintype "bidirectional"))
      (node (ref "X4") (pin "1") (pinfunction "KL_1") (pintype "passive"))
    )
    (net (code "66") (name "/RELAY5_14") (class "Default")
      (node (ref "S5") (pin "14") (pinfunction "14_14") (pintype "bidirectional"))
      (node (ref "X4") (pin "2") (pinfunction "KL_2") (pintype "passive"))
    )
    (net (code "67") (name "/RELAY6_11") (class "Default")
      (node (ref "S6") (pin "11") (pinfunction "11_11") (pintype "bidirectional"))
      (node (ref "X4") (pin "3") (pinfunction "KL_3") (pintype "passive"))
    )
    (net (code "68") (name "/RELAY6_14") (class "Default")
      (node (ref "S6") (pin "14") (pinfunction "14_14") (pintype "bidirectional"))
      (node (ref "X4") (pin "4") (pinfunction "KL_4") (pintype "passive"))
    )
    (net (code "69") (name "/RELAY7_11") (class "Default")
      (node (ref "S7") (pin "11") (pinfunction "11_11") (pintype "bidirectional"))
      (node (ref "X4") (pin "5") (pinfunction "KL_5") (pintype "passive"))
    )
    (net (code "70") (name "/RELAY7_14") (class "Default")
      (node (ref "S7") (pin "14") (pinfunction "14_14") (pintype "bidirectional"))
      (node (ref "X4") (pin "6") (pinfunction "KL_6") (pintype "passive"))
    )
    (net (code "71") (name "/RELAY8_11") (class "Default")
      (node (ref "S8") (pin "11") (pinfunction "11_11") (pintype "bidirectional"))
      (node (ref "X4") (pin "7") (pinfunction "KL_7") (pintype "passive"))
    )
    (net (code "72") (name "/RELAY8_14") (class "Default")
      (node (ref "S8") (pin "14") (pinfunction "14_14") (pintype "bidirectional"))
      (node (ref "X4") (pin "8") (pinfunction "KL_8") (pintype "passive"))
    )
    (net (code "73") (name "/RS485_A") (class "Default")
      (node (ref "R69") (pin "2") (pinfunction "2_2") (pintype "passive"))
      (node (ref "X2") (pin "8") (pinfunction "KL_8") (pintype "passive"))
    )
    (net (code "74") (name "/RS485_B") (class "Default")
      (node (ref "R68") (pin "2") (pinfunction "2_2") (pintype "passive"))
      (node (ref "X2") (pin "9") (pinfunction "KL_9") (pintype "passive"))
    )
    (net (code "75") (name "/RX") (class "Default")
      (node (ref "K1") (pin "35") (pinfunction "35_35") (pintype "passive"))
      (node (ref "R71") (pin "1") (pinfunction "1_1") (pintype "passive"))
      (node (ref "U6") (pin "1") (pinfunction "R_1") (pintype "input"))
    )
    (net (code "76") (name "/SCK") (class "Default")
      (node (ref "K4") (pin "2") (pinfunction "2_2") (pintype "passive"))
      (node (ref "U5") (pin "8") (pinfunction "SCK_8") (pintype "passive"))
    )
    (net (code "77") (name "/SCL") (class "Default")
      (node (ref "IC2") (pin "4") (pinfunction "SCL_4") (pintype "bidirectional"))
      (node (ref "K1") (pin "3") (pinfunction "3_3") (pintype "passive"))
      (node (ref "R25") (pin "1") (pinfunction "1_1") (pintype "passive"))
      (node (ref "U$2") (pin "45") (pinfunction "PB8/I2C1_SCL/TIM16_CH1/CAN_RX_45") (pintype "bidirectional"))
    )
    (net (code "78") (name "/SDA") (class "Default")
      (node (ref "IC2") (pin "5") (pinfunction "SDA_5") (pintype "bidirectional"))
      (node (ref "K1") (pin "4") (pinfunction "4_4") (pintype "passive"))
      (node (ref "R26") (pin "1") (pinfunction "1_1") (pintype "passive"))
      (node (ref "U$2") (pin "46") (pinfunction "PB9/I2C1_SDA/TIM17_CH1/CAN_TX_46") (pintype "bidirectional"))
    )
    (net (code "79") (name "/SWCLK") (class "Default")
      (node (ref "K5") (pin "2") (pinfunction "2_2") (pintype "passive"))
      (node (ref "U$2") (pin "37") (pinfunction "PA14/USART2_TX/SWCLK_37") (pintype "bidirectional"))
    )
    (net (code "80") (name "/SWDIO") (class "Default")
      (node (ref "K5") (pin "4") (pinfunction "4_4") (pintype "passive"))
      (node (ref "U$2") (pin "34") (pinfunction "PA13/SWDIO_34") (pintype "bidirectional"))
    )
    (net (code "81") (name "/TPIN+") (class "Default")
      (node (ref "R20") (pin "2") (pinfunction "2_2") (pintype "passive"))
      (node (ref "U5") (pin "13") (pinfunction "TPIN+_13") (pintype "passive"))
      (node (ref "X1") (pin "7") (pinfunction "RD+_7") (pintype "input"))
    )
    (net (code "82") (name "/TPIN-") (class "Default")
      (node (ref "R21") (pin "2") (pinfunction "2_2") (pintype "passive"))
      (node (ref "U5") (pin "12") (pinfunction "TPIN-_12") (pintype "passive"))
      (node (ref "X1") (pin "8") (pinfunction "RD-_8") (pintype "input"))
    )
    (net (code "83") (name "/TPOUT+") (class "Default")
      (node (ref "R18") (pin "2") (pinfunction "2_2") (pintype "passive"))
      (node (ref "U5") (pin "17") (pinfunction "TPOUT+_17") (pintype "passive"))
      (node (ref "X1") (pin "1") (pinfunction "TD+_1") (pintype "input"))
    )
    (net (code "84") (name "/TPOUT-") (class "Default")
      (node (ref "R19") (pin "2") (pinfunction "2_2") (pintype "passive"))
      (node (ref "U5") (pin "16") (pinfunction "TPOUT-_16") (pintype "passive"))
      (node (ref "X1") (pin "2") (pinfunction "TD-_2") (pintype "input"))
    )
    (net (code "85") (name "/TX") (class "Default")
      (node (ref "K1") (pin "34") (pinfunction "34_34") (pintype "passive"))
      (node (ref "R70") (pin "2") (pinfunction "2_2") (pintype "passive"))
      (node (ref "U6") (pin "4") (pinfunction "D_4") (pintype "input"))
    )
    (net (code "86") (name "/UC_BOOT") (class "Default")
      (node (ref "R24") (pin "2") (pinfunction "2_2") (pintype "passive"))
      (node (ref "U$2") (pin "44") (pinfunction "BOOT0(P44)_44") (pintype "bidirectional"))
    )
    (net (code "87") (name "/UC_INT") (class "Default")
      (node (ref "K1") (pin "5") (pinfunction "5_5") (pintype "passive"))
      (node (ref "U$2") (pin "27") (pinfunction "PB14/SPI2_MISO/I2C2_SDA_27") (pintype "bidirectional"))
    )
    (net (code "88") (name "/UC_NRST") (class "Default")
      (node (ref "K1") (pin "6") (pinfunction "6_6") (pintype "passive"))
      (node (ref "K5") (pin "5") (pinfunction "5_5") (pintype "passive"))
      (node (ref "R2") (pin "1") (pinfunction "1_1") (pintype "passive"))
      (node (ref "U$2") (pin "7") (pinfunction "NRST(P7)_7") (pintype "bidirectional"))
    )
    (net (code "89") (name "GND") (class "Default")
      (node (ref "C1") (pin "2") (pinfunction "2_2") (pintype "passive"))
      (node (ref "C10") (pin "2") (pinfunction "2_2") (pintype "passive"))
      (node (ref "C11") (pin "2") (pinfunction "2_2") (pintype "passive"))
      (node (ref "C12") (pin "2") (pinfunction "2_2") (pintype "passive"))
      (node (ref "C13") (pin "2") (pinfunction "2_2") (pintype "passive"))
      (node (ref "C14") (pin "-") (pinfunction "-_-") (pintype "passive"))
      (node (ref "C15") (pin "-") (pinfunction "-_-") (pintype "passive"))
      (node (ref "C16") (pin "2") (pinfunction "2_2") (pintype "passive"))
      (node (ref "C17") (pin "2") (pinfunction "2_2") (pintype "passive"))
      (node (ref "C18") (pin "2") (pinfunction "2_2") (pintype "passive"))
      (node (ref "C19") (pin "2") (pinfunction "2_2") (pintype "passive"))
      (node (ref "C2") (pin "2") (pinfunction "2_2") (pintype "passive"))
      (node (ref "C20") (pin "2") (pinfunction "2_2") (pintype "passive"))
      (node (ref "C21") (pin "2") (pinfunction "2_2") (pintype "passive"))
      (node (ref "C22") (pin "2") (pinfunction "2_2") (pintype "passive"))
      (node (ref "C23") (pin "2") (pinfunction "2_2") (pintype "passive"))
      (node (ref "C24") (pin "2") (pinfunction "2_2") (pintype "passive"))
      (node (ref "C25") (pin "2") (pinfunction "2_2") (pintype "passive"))
      (node (ref "C26") (pin "2") (pinfunction "2_2") (pintype "passive"))
      (node (ref "C27") (pin "2") (pinfunction "2_2") (pintype "passive"))
      (node (ref "C28") (pin "2") (pinfunction "2_2") (pintype "passive"))
      (node (ref "C29") (pin "2") (pinfunction "2_2") (pintype "passive"))
      (node (ref "C30") (pin "2") (pinfunction "2_2") (pintype "passive"))
      (node (ref "C31") (pin "2") (pinfunction "2_2") (pintype "passive"))
      (node (ref "C32") (pin "2") (pinfunction "2_2") (pintype "passive"))
      (node (ref "C33") (pin "1") (pinfunction "1_1") (pintype "passive"))
      (node (ref "C4") (pin "2") (pinfunction "2_2") (pintype "passive"))
      (node (ref "C5") (pin "2") (pinfunction "2_2") (pintype "passive"))
      (node (ref "C6") (pin "2") (pinfunction "2_2") (pintype "passive"))
      (node (ref "C7") (pin "2") (pinfunction "2_2") (pintype "passive"))
      (node (ref "C8") (pin "2") (pinfunction "2_2") (pintype "passive"))
      (node (ref "C9") (pin "2") (pinfunction "2_2") (pintype "passive"))
      (node (ref "D11") (pin "A") (pinfunction "A_A") (pintype "passive"))
      (node (ref "D13") (pin "A") (pinfunction "A_A") (pintype "passive"))
      (node (ref "D15") (pin "A") (pinfunction "A_A") (pintype "passive"))
      (node (ref "D17") (pin "A") (pinfunction "A_A") (pintype "passive"))
      (node (ref "D19") (pin "A") (pinfunction "A_A") (pintype "passive"))
      (node (ref "D2") (pin "A") (pinfunction "A_A") (pintype "passive"))
      (node (ref "D27") (pin "1") (pinfunction "A_1") (pintype "passive"))
      (node (ref "D28") (pin "1") (pinfunction "A_1") (pintype "passive"))
      (node (ref "D29") (pin "1") (pinfunction "A_1") (pintype "passive"))
      (node (ref "D30") (pin "1") (pinfunction "A_1") (pintype "passive"))
      (node (ref "D31") (pin "1") (pinfunction "A_1") (pintype "passive"))
      (node (ref "D32") (pin "1") (pinfunction "A_1") (pintype "passive"))
      (node (ref "D33") (pin "1") (pinfunction "A_1") (pintype "passive"))
      (node (ref "D34") (pin "1") (pinfunction "A_1") (pintype "passive"))
      (node (ref "D4") (pin "A") (pinfunction "A_A") (pintype "passive"))
      (node (ref "D5") (pin "A") (pinfunction "A_A") (pintype "passive"))
      (node (ref "D7") (pin "A") (pinfunction "A_A") (pintype "passive"))
      (node (ref "D9") (pin "A") (pinfunction "A_A") (pintype "passive"))
      (node (ref "IC1") (pin "3") (pinfunction "GND_3") (pintype "passive"))
      (node (ref "IC2") (pin "3") (pinfunction "GND_3") (pintype "power_in"))
      (node (ref "IC2") (pin "7") (pinfunction "AD1_7") (pintype "power_in"))
      (node (ref "IC2") (pin "8") (pinfunction "AD0_8") (pintype "power_in"))
      (node (ref "K1") (pin "40") (pinfunction "40_40") (pintype "passive"))
      (node (ref "K2") (pin "39") (pinfunction "39_39") (pintype "passive"))
      (node (ref "K2") (pin "40") (pinfunction "40_40") (pintype "passive"))
      (node (ref "K5") (pin "3") (pinfunction "3_3") (pintype "passive"))
      (node (ref "OK1") (pin "11") (pinfunction "EMIT_11") (pintype "passive"))
      (node (ref "OK1") (pin "13") (pinfunction "EMIT_13") (pintype "passive"))
      (node (ref "OK1") (pin "15") (pinfunction "EMIT_15") (pintype "passive"))
      (node (ref "OK1") (pin "2") (pinfunction "C_2") (pintype "passive"))
      (node (ref "OK1") (pin "4") (pinfunction "C_4") (pintype "passive"))
      (node (ref "OK1") (pin "6") (pinfunction "C_6") (pintype "passive"))
      (node (ref "OK1") (pin "8") (pinfunction "C_8") (pintype "passive"))
      (node (ref "OK1") (pin "9") (pinfunction "EMIT_9") (pintype "passive"))
      (node (ref "OK2") (pin "11") (pinfunction "EMIT_11") (pintype "passive"))
      (node (ref "OK2") (pin "13") (pinfunction "EMIT_13") (pintype "passive"))
      (node (ref "OK2") (pin "15") (pinfunction "EMIT_15") (pintype "passive"))
      (node (ref "OK2") (pin "2") (pinfunction "C_2") (pintype "passive"))
      (node (ref "OK2") (pin "4") (pinfunction "C_4") (pintype "passive"))
      (node (ref "OK2") (pin "6") (pinfunction "C_6") (pintype "passive"))
      (node (ref "OK2") (pin "8") (pinfunction "C_8") (pintype "passive"))
      (node (ref "OK2") (pin "9") (pinfunction "EMIT_9") (pintype "passive"))
      (node (ref "Q1") (pin "2") (pinfunction "S_2") (pintype "passive"))
      (node (ref "Q10") (pin "2") (pinfunction "S_2") (pintype "passive"))
      (node (ref "Q11") (pin "2") (pinfunction "S_2") (pintype "passive"))
      (node (ref "Q4") (pin "2") (pinfunction "S_2") (pintype "passive"))
      (node (ref "Q5") (pin "2") (pinfunction "S_2") (pintype "passive"))
      (node (ref "Q6") (pin "2") (pinfunction "S_2") (pintype "passive"))
      (node (ref "Q7") (pin "2") (pinfunction "S_2") (pintype "passive"))
      (node (ref "Q8") (pin "2") (pinfunction "S_2") (pintype "passive"))
      (node (ref "Q9") (pin "2") (pinfunction "S_2") (pintype "passive"))
      (node (ref "QF1") (pin "2") (pinfunction "2_2") (pintype "passive"))
      (node (ref "R1") (pin "1") (pinfunction "1_1") (pintype "passive"))
      (node (ref "R12") (pin "1") (pinfunction "1_1") (pintype "passive"))
      (node (ref "R13") (pin "1") (pinfunction "1_1") (pintype "passive"))
      (node (ref "R15") (pin "1") (pinfunction "1_1") (pintype "passive"))
      (node (ref "R16") (pin "2") (pinfunction "2_2") (pintype "passive"))
      (node (ref "R24") (pin "1") (pinfunction "1_1") (pintype "passive"))
      (node (ref "R27") (pin "1") (pinfunction "1_1") (pintype "passive"))
      (node (ref "R35") (pin "1") (pinfunction "1_1") (pintype "passive"))
      (node (ref "R40") (pin "1") (pinfunction "1_1") (pintype "passive"))
      (node (ref "R42") (pin "1") (pinfunction "1_1") (pintype "passive"))
      (node (ref "R44") (pin "1") (pinfunction "1_1") (pintype "passive"))
      (node (ref "R46") (pin "1") (pinfunction "1_1") (pintype "passive"))
      (node (ref "R6") (pin "1") (pinfunction "1_1") (pintype "passive"))
      (node (ref "R61") (pin "1") (pinfunction "1_1") (pintype "passive"))
      (node (ref "R62") (pin "1") (pinfunction "1_1") (pintype "passive"))
      (node (ref "R63") (pin "1") (pinfunction "1_1") (pintype "passive"))
      (node (ref "R64") (pin "1") (pinfunction "1_1") (pintype "passive"))
      (node (ref "R65") (pin "1") (pinfunction "1_1") (pintype "passive"))
      (node (ref "R66") (pin "1") (pinfunction "1_1") (pintype "passive"))
      (node (ref "R67") (pin "1") (pinfunction "1_1") (pintype "passive"))
      (node (ref "U$1") (pin "GND") (pinfunction "GND_GND") (pintype "power_in"))
      (node (ref "U$2") (pin "23") (pinfunction "VSS_1(P23)_23") (pintype "bidirectional"))
      (node (ref "U$2") (pin "35") (pinfunction "VSS_2(P35)_35") (pintype "bidirectional"))
      (node (ref "U$2") (pin "47") (pinfunction "VSS_3(P47)_47") (pintype "bidirectional"))
      (node (ref "U$2") (pin "8") (pinfunction "VSSA(P8)_8") (pintype "bidirectional"))
      (node (ref "U1") (pin "6") (pinfunction "GND_6") (pintype "passive"))
      (node (ref "U3") (pin "4") (pinfunction "GND_4") (pintype "passive"))
      (node (ref "U4") (pin "4") (pinfunction "GND_4") (pintype "passive"))
      (node (ref "U5") (pin "11") (pinfunction "VSSRX_11") (pintype "power_in"))
      (node (ref "U5") (pin "18") (pinfunction "VSSTX_18") (pintype "power_in"))
      (node (ref "U5") (pin "2") (pinfunction "VSS_2") (pintype "power_in"))
      (node (ref "U5") (pin "21") (pinfunction "VSSPLL_21") (pintype "power_in"))
      (node (ref "U5") (pin "22") (pinfunction "VSSOSC_22") (pintype "power_in"))
      (node (ref "U6") (pin "5") (pinfunction "GND_5") (pintype "passive"))
      (node (ref "X2") (pin "10") (pinfunction "KL_10") (pintype "passive"))
      (node (ref "X2") (pin "3") (pinfunction "KL_3") (pintype "passive"))
      (node (ref "X2") (pin "4") (pinfunction "KL_4") (pintype "passive"))
      (node (ref "X2") (pin "5") (pinfunction "KL_5") (pintype "passive"))
      (node (ref "X2") (pin "7") (pinfunction "KL_7") (pintype "passive"))
      (node (ref "X3") (pin "1") (pinfunction "KL_1") (pintype "passive"))
      (node (ref "X3") (pin "2") (pinfunction "KL_2") (pintype "passive"))
      (node (ref "X4") (pin "10") (pinfunction "KL_10") (pintype "passive"))
      (node (ref "X4") (pin "9") (pinfunction "KL_9") (pintype "passive"))
      (node (ref "X5") (pin "10") (pinfunction "KL_10") (pintype "passive"))
      (node (ref "X5") (pin "5") (pinfunction "KL_5") (pintype "passive"))
      (node (ref "X6") (pin "10") (pinfunction "KL_10") (pintype "passive"))
      (node (ref "X6") (pin "5") (pinfunction "KL_5") (pintype "passive"))
    )
    (net (code "90") (name "Net-(C1-Pad1)") (class "Default")
      (node (ref "C1") (pin "1") (pinfunction "1_1") (pintype "passive"))
      (node (ref "R3") (pin "2") (pinfunction "2_2") (pintype "passive"))
      (node (ref "R4") (pin "1") (pinfunction "1_1") (pintype "passive"))
    )
    (net (code "91") (name "Net-(C7-Pad1)") (class "Default")
      (node (ref "C7") (pin "1") (pinfunction "1_1") (pintype "passive"))
      (node (ref "R10") (pin "1") (pinfunction "1_1") (pintype "passive"))
      (node (ref "R9") (pin "2") (pinfunction "2_2") (pintype "passive"))
    )
    (net (code "92") (name "Net-(C9-Pad1)") (class "Default")
      (node (ref "C9") (pin "1") (pinfunction "1_1") (pintype "passive"))
      (node (ref "R14") (pin "2") (pinfunction "2_2") (pintype "passive"))
      (node (ref "R22") (pin "1") (pinfunction "1_1") (pintype "passive"))
    )
    (net (code "93") (name "Net-(C11-Pad1)") (class "Default")
      (node (ref "C11") (pin "1") (pinfunction "1_1") (pintype "passive"))
      (node (ref "R28") (pin "2") (pinfunction "2_2") (pintype "passive"))
      (node (ref "R29") (pin "1") (pinfunction "1_1") (pintype "passive"))
    )
    (net (code "94") (name "Net-(C32-Pad1)") (class "Default")
      (node (ref "C32") (pin "1") (pinfunction "1_1") (pintype "passive"))
      (node (ref "R20") (pin "1") (pinfunction "1_1") (pintype "passive"))
      (node (ref "R21") (pin "1") (pinfunction "1_1") (pintype "passive"))
    )
    (net (code "95") (name "Net-(D3-PadC)") (class "Default")
      (node (ref "D3") (pin "C") (pinfunction "C_C") (pintype "passive"))
      (node (ref "R8") (pin "1") (pinfunction "1_1") (pintype "passive"))
    )
    (net (code "96") (name "Net-(D6-PadC)") (class "Default")
      (node (ref "D6") (pin "C") (pinfunction "C_C") (pintype "passive"))
      (node (ref "R48") (pin "1") (pinfunction "1_1") (pintype "passive"))
    )
    (net (code "97") (name "Net-(D8-PadC)") (class "Default")
      (node (ref "D8") (pin "C") (pinfunction "C_C") (pintype "passive"))
      (node (ref "R50") (pin "1") (pinfunction "1_1") (pintype "passive"))
    )
    (net (code "98") (name "Net-(D10-PadC)") (class "Default")
      (node (ref "D10") (pin "C") (pinfunction "C_C") (pintype "passive"))
      (node (ref "R52") (pin "1") (pinfunction "1_1") (pintype "passive"))
    )
    (net (code "99") (name "Net-(D12-PadC)") (class "Default")
      (node (ref "D12") (pin "C") (pinfunction "C_C") (pintype "passive"))
      (node (ref "R54") (pin "1") (pinfunction "1_1") (pintype "passive"))
    )
    (net (code "100") (name "Net-(D14-PadC)") (class "Default")
      (node (ref "D14") (pin "C") (pinfunction "C_C") (pintype "passive"))
      (node (ref "R56") (pin "1") (pinfunction "1_1") (pintype "passive"))
    )
    (net (code "101") (name "Net-(D16-PadC)") (class "Default")
      (node (ref "D16") (pin "C") (pinfunction "C_C") (pintype "passive"))
      (node (ref "R58") (pin "1") (pinfunction "1_1") (pintype "passive"))
    )
    (net (code "102") (name "Net-(D18-PadC)") (class "Default")
      (node (ref "D18") (pin "C") (pinfunction "C_C") (pintype "passive"))
      (node (ref "R60") (pin "1") (pinfunction "1_1") (pintype "passive"))
    )
    (net (code "103") (name "Net-(IC2-PCTLZ)") (class "Default")
      (node (ref "IC2") (pin "6") (pinfunction "PCTLZ_6") (pintype "bidirectional"))
      (node (ref "Q12") (pin "1") (pinfunction "G_1") (pintype "passive"))
    )
    (net (code "104") (name "Net-(OK1A-A)") (class "Default")
      (node (ref "D3") (pin "A") (pinfunction "A_A") (pintype "passive"))
      (node (ref "D4") (pin "C") (pinfunction "C_C") (pintype "passive"))
      (node (ref "OK1") (pin "1") (pinfunction "A_1") (pintype "passive"))
    )
    (net (code "105") (name "Net-(OK1B-A)") (class "Default")
      (node (ref "D6") (pin "A") (pinfunction "A_A") (pintype "passive"))
      (node (ref "D7") (pin "C") (pinfunction "C_C") (pintype "passive"))
      (node (ref "OK1") (pin "3") (pinfunction "A_3") (pintype "passive"))
    )
    (net (code "106") (name "Net-(OK1C-A)") (class "Default")
      (node (ref "D8") (pin "A") (pinfunction "A_A") (pintype "passive"))
      (node (ref "D9") (pin "C") (pinfunction "C_C") (pintype "passive"))
      (node (ref "OK1") (pin "5") (pinfunction "A_5") (pintype "passive"))
    )
    (net (code "107") (name "Net-(OK1D-A)") (class "Default")
      (node (ref "D10") (pin "A") (pinfunction "A_A") (pintype "passive"))
      (node (ref "D11") (pin "C") (pinfunction "C_C") (pintype "passive"))
      (node (ref "OK1") (pin "7") (pinfunction "A_7") (pintype "passive"))
    )
    (net (code "108") (name "Net-(OK2A-A)") (class "Default")
      (node (ref "D12") (pin "A") (pinfunction "A_A") (pintype "passive"))
      (node (ref "D13") (pin "C") (pinfunction "C_C") (pintype "passive"))
      (node (ref "OK2") (pin "1") (pinfunction "A_1") (pintype "passive"))
    )
    (net (code "109") (name "Net-(OK2B-A)") (class "Default")
      (node (ref "D14") (pin "A") (pinfunction "A_A") (pintype "passive"))
      (node (ref "D15") (pin "C") (pinfunction "C_C") (pintype "passive"))
      (node (ref "OK2") (pin "3") (pinfunction "A_3") (pintype "passive"))
    )
    (net (code "110") (name "Net-(OK2C-A)") (class "Default")
      (node (ref "D16") (pin "A") (pinfunction "A_A") (pintype "passive"))
      (node (ref "D17") (pin "C") (pinfunction "C_C") (pintype "passive"))
      (node (ref "OK2") (pin "5") (pinfunction "A_5") (pintype "passive"))
    )
    (net (code "111") (name "Net-(OK2D-A)") (class "Default")
      (node (ref "D18") (pin "A") (pinfunction "A_A") (pintype "passive"))
      (node (ref "D19") (pin "C") (pinfunction "C_C") (pintype "passive"))
      (node (ref "OK2") (pin "7") (pinfunction "A_7") (pintype "passive"))
    )
    (net (code "112") (name "Net-(Q1-D)") (class "Default")
      (node (ref "D1") (pin "A") (pinfunction "A_A") (pintype "passive"))
      (node (ref "Q1") (pin "3") (pinfunction "D_3") (pintype "passive"))
      (node (ref "S1") (pin "A2") (pinfunction "A2_A2") (pintype "bidirectional"))
    )
    (net (code "113") (name "Net-(Q4-D)") (class "Default")
      (node (ref "D20") (pin "A") (pinfunction "A_A") (pintype "passive"))
      (node (ref "Q4") (pin "3") (pinfunction "D_3") (pintype "passive"))
      (node (ref "S2") (pin "A2") (pinfunction "A2_A2") (pintype "bidirectional"))
    )
    (net (code "114") (name "Net-(Q5-D)") (class "Default")
      (node (ref "D21") (pin "A") (pinfunction "A_A") (pintype "passive"))
      (node (ref "Q5") (pin "3") (pinfunction "D_3") (pintype "passive"))
      (node (ref "S3") (pin "A2") (pinfunction "A2_A2") (pintype "bidirectional"))
    )
    (net (code "115") (name "Net-(Q6-D)") (class "Default")
      (node (ref "D22") (pin "A") (pinfunction "A_A") (pintype "passive"))
      (node (ref "Q6") (pin "3") (pinfunction "D_3") (pintype "passive"))
      (node (ref "S4") (pin "A2") (pinfunction "A2_A2") (pintype "bidirectional"))
    )
    (net (code "116") (name "Net-(Q7-D)") (class "Default")
      (node (ref "D23") (pin "A") (pinfunction "A_A") (pintype "passive"))
      (node (ref "Q7") (pin "3") (pinfunction "D_3") (pintype "passive"))
      (node (ref "S5") (pin "A2") (pinfunction "A2_A2") (pintype "bidirectional"))
    )
    (net (code "117") (name "Net-(Q8-D)") (class "Default")
      (node (ref "D24") (pin "A") (pinfunction "A_A") (pintype "passive"))
      (node (ref "Q8") (pin "3") (pinfunction "D_3") (pintype "passive"))
      (node (ref "S6") (pin "A2") (pinfunction "A2_A2") (pintype "bidirectional"))
    )
    (net (code "118") (name "Net-(Q9-D)") (class "Default")
      (node (ref "D25") (pin "A") (pinfunction "A_A") (pintype "passive"))
      (node (ref "Q9") (pin "3") (pinfunction "D_3") (pintype "passive"))
      (node (ref "S7") (pin "A2") (pinfunction "A2_A2") (pintype "bidirectional"))
    )
    (net (code "119") (name "Net-(Q10-D)") (class "Default")
      (node (ref "D26") (pin "A") (pinfunction "A_A") (pintype "passive"))
      (node (ref "Q10") (pin "3") (pinfunction "D_3") (pintype "passive"))
      (node (ref "S8") (pin "A2") (pinfunction "A2_A2") (pintype "bidirectional"))
    )
    (net (code "120") (name "Net-(Q11-G)") (class "Default")
      (node (ref "Q11") (pin "1") (pinfunction "G_1") (pintype "passive"))
      (node (ref "R70") (pin "1") (pinfunction "1_1") (pintype "passive"))
    )
    (net (code "121") (name "Net-(Q12-S)") (class "Default")
      (node (ref "Q12") (pin "2") (pinfunction "S_2") (pintype "passive"))
      (node (ref "R31") (pin "1") (pinfunction "1_1") (pintype "passive"))
    )
    (net (code "122") (name "Net-(U$2-VBATT(P1))") (class "Default")
      (node (ref "U$1") (pin "V+") (pinfunction "V+_V+") (pintype "power_in"))
      (node (ref "U$2") (pin "1") (pinfunction "VBATT(P1)_1") (pintype "bidirectional"))
    )
    (net (code "123") (name "Net-(U1-CB)") (class "Default")
      (node (ref "C3") (pin "2") (pinfunction "2_2") (pintype "passive"))
      (node (ref "U1") (pin "1") (pinfunction "CB_1") (pintype "passive"))
    )
    (net (code "124") (name "Net-(U1-VSW)") (class "Default")
      (node (ref "C3") (pin "1") (pinfunction "1_1") (pintype "passive"))
      (node (ref "D2") (pin "C") (pinfunction "C_C") (pintype "passive"))
      (node (ref "L1") (pin "2") (pinfunction "2_2") (pintype "passive"))
      (node (ref "U1") (pin "8") (pinfunction "VSW_8") (pintype "passive"))
    )
    (net (code "125") (name "Net-(U3-1IN+)") (class "Default")
      (node (ref "C2") (pin "1") (pinfunction "1_1") (pintype "passive"))
      (node (ref "R4") (pin "2") (pinfunction "2_2") (pintype "passive"))
      (node (ref "U3") (pin "3") (pinfunction "1IN+_3") (pintype "input"))
    )
    (net (code "126") (name "Net-(U3-1IN-)") (class "Default")
      (node (ref "R5") (pin "1") (pinfunction "1_1") (pintype "passive"))
      (node (ref "R6") (pin "2") (pinfunction "2_2") (pintype "passive"))
      (node (ref "U3") (pin "2") (pinfunction "1IN-_2") (pintype "input"))
    )
    (net (code "127") (name "Net-(U3-2IN+)") (class "Default")
      (node (ref "C8") (pin "1") (pinfunction "1_1") (pintype "passive"))
      (node (ref "R10") (pin "2") (pinfunction "2_2") (pintype "passive"))
      (node (ref "U3") (pin "5") (pinfunction "2IN+_5") (pintype "input"))
    )
    (net (code "128") (name "Net-(U3-2IN-)") (class "Default")
      (node (ref "R11") (pin "1") (pinfunction "1_1") (pintype "passive"))
      (node (ref "R13") (pin "2") (pinfunction "2_2") (pintype "passive"))
      (node (ref "U3") (pin "6") (pinfunction "2IN-_6") (pintype "input"))
    )
    (net (code "129") (name "Net-(U4-1IN+)") (class "Default")
      (node (ref "C10") (pin "1") (pinfunction "1_1") (pintype "passive"))
      (node (ref "R22") (pin "2") (pinfunction "2_2") (pintype "passive"))
      (node (ref "U4") (pin "3") (pinfunction "1IN+_3") (pintype "input"))
    )
    (net (code "130") (name "Net-(U4-1IN-)") (class "Default")
      (node (ref "R23") (pin "1") (pinfunction "1_1") (pintype "passive"))
      (node (ref "R27") (pin "2") (pinfunction "2_2") (pintype "passive"))
      (node (ref "U4") (pin "2") (pinfunction "1IN-_2") (pintype "input"))
    )
    (net (code "131") (name "Net-(U4-2IN+)") (class "Default")
      (node (ref "C12") (pin "1") (pinfunction "1_1") (pintype "passive"))
      (node (ref "R29") (pin "2") (pinfunction "2_2") (pintype "passive"))
      (node (ref "U4") (pin "5") (pinfunction "2IN+_5") (pintype "input"))
    )
    (net (code "132") (name "Net-(U4-2IN-)") (class "Default")
      (node (ref "R30") (pin "1") (pinfunction "1_1") (pintype "passive"))
      (node (ref "R35") (pin "2") (pinfunction "2_2") (pintype "passive"))
      (node (ref "U4") (pin "6") (pinfunction "2IN-_6") (pintype "input"))
    )
    (net (code "133") (name "Net-(U5-RBIAS)") (class "Default")
      (node (ref "R16") (pin "1") (pinfunction "1_1") (pintype "passive"))
      (node (ref "U5") (pin "14") (pinfunction "RBIAS_14") (pintype "passive"))
    )
    (net (code "134") (name "Net-(U5-VCAP)") (class "Default")
      (node (ref "C23") (pin "1") (pinfunction "1_1") (pintype "passive"))
      (node (ref "U5") (pin "1") (pinfunction "VCAP_1") (pintype "power_in"))
    )
    (net (code "135") (name "Net-(U6-A)") (class "Default")
      (node (ref "R69") (pin "1") (pinfunction "1_1") (pintype "passive"))
      (node (ref "U6") (pin "6") (pinfunction "A_6") (pintype "output"))
    )
    (net (code "136") (name "Net-(U6-B)") (class "Default")
      (node (ref "R68") (pin "1") (pinfunction "1_1") (pintype "passive"))
      (node (ref "U6") (pin "7") (pinfunction "B_7") (pintype "output"))
    )
    (net (code "137") (name "Net-(X1-C-L)") (class "Default")
      (node (ref "R15") (pin "2") (pinfunction "2_2") (pintype "passive"))
      (node (ref "X1") (pin "11") (pinfunction "C-L_11") (pintype "passive"))
    )
    (net (code "138") (name "Net-(X1-C-R)") (class "Default")
      (node (ref "R12") (pin "2") (pinfunction "2_2") (pintype "passive"))
      (node (ref "X1") (pin "10") (pinfunction "C-R_10") (pintype "passive"))
    )
    (net (code "139") (name "VCC") (class "Default")
      (node (ref "C13") (pin "1") (pinfunction "1_1") (pintype "passive"))
      (node (ref "C14") (pin "+") (pinfunction "+_+") (pintype "passive"))
      (node (ref "D1") (pin "C") (pinfunction "C_C") (pintype "passive"))
      (node (ref "D20") (pin "C") (pinfunction "C_C") (pintype "passive"))
      (node (ref "D21") (pin "C") (pinfunction "C_C") (pintype "passive"))
      (node (ref "D22") (pin "C") (pinfunction "C_C") (pintype "passive"))
      (node (ref "D23") (pin "C") (pinfunction "C_C") (pintype "passive"))
      (node (ref "D24") (pin "C") (pinfunction "C_C") (pintype "passive"))
      (node (ref "D25") (pin "C") (pinfunction "C_C") (pintype "passive"))
      (node (ref "D26") (pin "C") (pinfunction "C_C") (pintype "passive"))
      (node (ref "D5") (pin "C") (pinfunction "C_C") (pintype "passive"))
      (node (ref "F1") (pin "2") (pinfunction "2_2") (pintype "passive"))
      (node (ref "IC1") (pin "1") (pinfunction "VI_1") (pintype "input"))
      (node (ref "S1") (pin "A1") (pinfunction "A1_A1") (pintype "bidirectional"))
      (node (ref "S2") (pin "A1") (pinfunction "A1_A1") (pintype "bidirectional"))
      (node (ref "S3") (pin "A1") (pinfunction "A1_A1") (pintype "bidirectional"))
      (node (ref "S4") (pin "A1") (pinfunction "A1_A1") (pintype "bidirectional"))
      (node (ref "S5") (pin "A1") (pinfunction "A1_A1") (pintype "bidirectional"))
      (node (ref "S6") (pin "A1") (pinfunction "A1_A1") (pintype "bidirectional"))
      (node (ref "S7") (pin "A1") (pinfunction "A1_A1") (pintype "bidirectional"))
      (node (ref "S8") (pin "A1") (pinfunction "A1_A1") (pintype "bidirectional"))
      (node (ref "U1") (pin "7") (pinfunction "VIN_7") (pintype "power_in"))
    )
    (net (code "140") (name "unconnected-(K1-Pad2)") (class "Default")
      (node (ref "K1") (pin "2") (pinfunction "2_2") (pintype "passive"))
    )
    (net (code "141") (name "unconnected-(K1-Pad9)") (class "Default")
      (node (ref "K1") (pin "9") (pinfunction "9_9") (pintype "passive"))
    )
    (net (code "142") (name "unconnected-(K1-Pad10)") (class "Default")
      (node (ref "K1") (pin "10") (pinfunction "10_10") (pintype "passive"))
    )
    (net (code "143") (name "unconnected-(K1-Pad11)") (class "Default")
      (node (ref "K1") (pin "11") (pinfunction "11_11") (pintype "passive"))
    )
    (net (code "144") (name "unconnected-(K1-Pad12)") (class "Default")
      (node (ref "K1") (pin "12") (pinfunction "12_12") (pintype "passive"))
    )
    (net (code "145") (name "unconnected-(K1-Pad13)") (class "Default")
      (node (ref "K1") (pin "13") (pinfunction "13_13") (pintype "passive"))
    )
    (net (code "146") (name "unconnected-(K1-Pad14)") (class "Default")
      (node (ref "K1") (pin "14") (pinfunction "14_14") (pintype "passive"))
    )
    (net (code "147") (name "unconnected-(K1-Pad15)") (class "Default")
      (node (ref "K1") (pin "15") (pinfunction "15_15") (pintype "passive"))
    )
    (net (code "148") (name "unconnected-(K1-Pad16)") (class "Default")
      (node (ref "K1") (pin "16") (pinfunction "16_16") (pintype "passive"))
    )
    (net (code "149") (name "unconnected-(K1-Pad17)") (class "Default")
      (node (ref "K1") (pin "17") (pinfunction "17_17") (pintype "passive"))
    )
    (net (code "150") (name "unconnected-(K1-Pad18)") (class "Default")
      (node (ref "K1") (pin "18") (pinfunction "18_18") (pintype "passive"))
    )
    (net (code "151") (name "unconnected-(K1-Pad19)") (class "Default")
      (node (ref "K1") (pin "19") (pinfunction "19_19") (pintype "passive"))
    )
    (net (code "152") (name "unconnected-(K1-Pad20)") (class "Default")
      (node (ref "K1") (pin "20") (pinfunction "20_20") (pintype "passive"))
    )
    (net (code "153") (name "unconnected-(K1-Pad21)") (class "Default")
      (node (ref "K1") (pin "21") (pinfunction "21_21") (pintype "passive"))
    )
    (net (code "154") (name "unconnected-(K1-Pad22)") (class "Default")
      (node (ref "K1") (pin "22") (pinfunction "22_22") (pintype "passive"))
    )
    (net (code "155") (name "unconnected-(K1-Pad23)") (class "Default")
      (node (ref "K1") (pin "23") (pinfunction "23_23") (pintype "passive"))
    )
    (net (code "156") (name "unconnected-(K1-Pad24)") (class "Default")
      (node (ref "K1") (pin "24") (pinfunction "24_24") (pintype "passive"))
    )
    (net (code "157") (name "unconnected-(K1-Pad25)") (class "Default")
      (node (ref "K1") (pin "25") (pinfunction "25_25") (pintype "passive"))
    )
    (net (code "158") (name "unconnected-(K1-Pad26)") (class "Default")
      (node (ref "K1") (pin "26") (pinfunction "26_26") (pintype "passive"))
    )
    (net (code "159") (name "unconnected-(K1-Pad27)") (class "Default")
      (node (ref "K1") (pin "27") (pinfunction "27_27") (pintype "passive"))
    )
    (net (code "160") (name "unconnected-(K1-Pad28)") (class "Default")
      (node (ref "K1") (pin "28") (pinfunction "28_28") (pintype "passive"))
    )
    (net (code "161") (name "unconnected-(K1-Pad29)") (class "Default")
      (node (ref "K1") (pin "29") (pinfunction "29_29") (pintype "passive"))
    )
    (net (code "162") (name "unconnected-(K1-Pad30)") (class "Default")
      (node (ref "K1") (pin "30") (pinfunction "30_30") (pintype "passive"))
    )
    (net (code "163") (name "unconnected-(K1-Pad31)") (class "Default")
      (node (ref "K1") (pin "31") (pinfunction "31_31") (pintype "passive"))
    )
    (net (code "164") (name "unconnected-(K1-Pad32)") (class "Default")
      (node (ref "K1") (pin "32") (pinfunction "32_32") (pintype "passive"))
    )
    (net (code "165") (name "unconnected-(K1-Pad33)") (class "Default")
      (node (ref "K1") (pin "33") (pinfunction "33_33") (pintype "passive"))
    )
    (net (code "166") (name "unconnected-(K1-Pad36)") (class "Default")
      (node (ref "K1") (pin "36") (pinfunction "36_36") (pintype "passive"))
    )
    (net (code "167") (name "unconnected-(K1-Pad37)") (class "Default")
      (node (ref "K1") (pin "37") (pinfunction "37_37") (pintype "passive"))
    )
    (net (code "168") (name "unconnected-(K1-Pad38)") (class "Default")
      (node (ref "K1") (pin "38") (pinfunction "38_38") (pintype "passive"))
    )
    (net (code "169") (name "unconnected-(K1-Pad39)") (class "Default")
      (node (ref "K1") (pin "39") (pinfunction "39_39") (pintype "passive"))
    )
    (net (code "170") (name "unconnected-(K2-Pad1)") (class "Default")
      (node (ref "K2") (pin "1") (pinfunction "1_1") (pintype "passive"))
    )
    (net (code "171") (name "unconnected-(K2-Pad2)") (class "Default")
      (node (ref "K2") (pin "2") (pinfunction "2_2") (pintype "passive"))
    )
    (net (code "172") (name "unconnected-(K2-Pad3)") (class "Default")
      (node (ref "K2") (pin "3") (pinfunction "3_3") (pintype "passive"))
    )
    (net (code "173") (name "unconnected-(K2-Pad4)") (class "Default")
      (node (ref "K2") (pin "4") (pinfunction "4_4") (pintype "passive"))
    )
    (net (code "174") (name "unconnected-(K2-Pad5)") (class "Default")
      (node (ref "K2") (pin "5") (pinfunction "5_5") (pintype "passive"))
    )
    (net (code "175") (name "unconnected-(K2-Pad6)") (class "Default")
      (node (ref "K2") (pin "6") (pinfunction "6_6") (pintype "passive"))
    )
    (net (code "176") (name "unconnected-(K2-Pad7)") (class "Default")
      (node (ref "K2") (pin "7") (pinfunction "7_7") (pintype "passive"))
    )
    (net (code "177") (name "unconnected-(K2-Pad8)") (class "Default")
      (node (ref "K2") (pin "8") (pinfunction "8_8") (pintype "passive"))
    )
    (net (code "178") (name "unconnected-(K2-Pad9)") (class "Default")
      (node (ref "K2") (pin "9") (pinfunction "9_9") (pintype "passive"))
    )
    (net (code "179") (name "unconnected-(K2-Pad10)") (class "Default")
      (node (ref "K2") (pin "10") (pinfunction "10_10") (pintype "passive"))
    )
    (net (code "180") (name "unconnected-(K2-Pad11)") (class "Default")
      (node (ref "K2") (pin "11") (pinfunction "11_11") (pintype "passive"))
    )
    (net (code "181") (name "unconnected-(K2-Pad12)") (class "Default")
      (node (ref "K2") (pin "12") (pinfunction "12_12") (pintype "passive"))
    )
    (net (code "182") (name "unconnected-(K2-Pad13)") (class "Default")
      (node (ref "K2") (pin "13") (pinfunction "13_13") (pintype "passive"))
    )
    (net (code "183") (name "unconnected-(K2-Pad14)") (class "Default")
      (node (ref "K2") (pin "14") (pinfunction "14_14") (pintype "passive"))
    )
    (net (code "184") (name "unconnected-(K2-Pad15)") (class "Default")
      (node (ref "K2") (pin "15") (pinfunction "15_15") (pintype "passive"))
    )
    (net (code "185") (name "unconnected-(K2-Pad16)") (class "Default")
      (node (ref "K2") (pin "16") (pinfunction "16_16") (pintype "passive"))
    )
    (net (code "186") (name "unconnected-(K2-Pad17)") (class "Default")
      (node (ref "K2") (pin "17") (pinfunction "17_17") (pintype "passive"))
    )
    (net (code "187") (name "unconnected-(K2-Pad18)") (class "Default")
      (node (ref "K2") (pin "18") (pinfunction "18_18") (pintype "passive"))
    )
    (net (code "188") (name "unconnected-(K2-Pad19)") (class "Default")
      (node (ref "K2") (pin "19") (pinfunction "19_19") (pintype "passive"))
    )
    (net (code "189") (name "unconnected-(K2-Pad20)") (class "Default")
      (node (ref "K2") (pin "20") (pinfunction "20_20") (pintype "passive"))
    )
    (net (code "190") (name "unconnected-(K2-Pad21)") (class "Default")
      (node (ref "K2") (pin "21") (pinfunction "21_21") (pintype "passive"))
    )
    (net (code "191") (name "unconnected-(K2-Pad22)") (class "Default")
      (node (ref "K2") (pin "22") (pinfunction "22_22") (pintype "passive"))
    )
    (net (code "192") (name "unconnected-(K2-Pad23)") (class "Default")
      (node (ref "K2") (pin "23") (pinfunction "23_23") (pintype "passive"))
    )
    (net (code "193") (name "unconnected-(K2-Pad24)") (class "Default")
      (node (ref "K2") (pin "24") (pinfunction "24_24") (pintype "passive"))
    )
    (net (code "194") (name "unconnected-(K2-Pad25)") (class "Default")
      (node (ref "K2") (pin "25") (pinfunction "25_25") (pintype "passive"))
    )
    (net (code "195") (name "unconnected-(K2-Pad26)") (class "Default")
      (node (ref "K2") (pin "26") (pinfunction "26_26") (pintype "passive"))
    )
    (net (code "196") (name "unconnected-(K2-Pad27)") (class "Default")
      (node (ref "K2") (pin "27") (pinfunction "27_27") (pintype "passive"))
    )
    (net (code "197") (name "unconnected-(K2-Pad28)") (class "Default")
      (node (ref "K2") (pin "28") (pinfunction "28_28") (pintype "passive"))
    )
    (net (code "198") (name "unconnected-(K2-Pad29)") (class "Default")
      (node (ref "K2") (pin "29") (pinfunction "29_29") (pintype "passive"))
    )
    (net (code "199") (name "unconnected-(K2-Pad30)") (class "Default")
      (node (ref "K2") (pin "30") (pinfunction "30_30") (pintype "passive"))
    )
    (net (code "200") (name "unconnected-(K2-Pad31)") (class "Default")
      (node (ref "K2") (pin "31") (pinfunction "31_31") (pintype "passive"))
    )
    (net (code "201") (name "unconnected-(K2-Pad32)") (class "Default")
      (node (ref "K2") (pin "32") (pinfunction "32_32") (pintype "passive"))
    )
    (net (code "202") (name "unconnected-(K2-Pad33)") (class "Default")
      (node (ref "K2") (pin "33") (pinfunction "33_33") (pintype "passive"))
    )
    (net (code "203") (name "unconnected-(K2-Pad34)") (class "Default")
      (node (ref "K2") (pin "34") (pinfunction "34_34") (pintype "passive"))
    )
    (net (code "204") (name "unconnected-(K2-Pad35)") (class "Default")
      (node (ref "K2") (pin "35") (pinfunction "35_35") (pintype "passive"))
    )
    (net (code "205") (name "unconnected-(K2-Pad36)") (class "Default")
      (node (ref "K2") (pin "36") (pinfunction "36_36") (pintype "passive"))
    )
    (net (code "206") (name "unconnected-(K2-Pad37)") (class "Default")
      (node (ref "K2") (pin "37") (pinfunction "37_37") (pintype "passive"))
    )
    (net (code "207") (name "unconnected-(K2-Pad38)") (class "Default")
      (node (ref "K2") (pin "38") (pinfunction "38_38") (pintype "passive"))
    )
    (net (code "208") (name "unconnected-(K4-Pad5)") (class "Default")
      (node (ref "K4") (pin "5") (pinfunction "5_5") (pintype "passive"))
    )
    (net (code "209") (name "unconnected-(K4-Pad6)") (class "Default")
      (node (ref "K4") (pin "6") (pinfunction "6_6") (pintype "passive"))
    )
    (net (code "210") (name "unconnected-(K4-Pad7)") (class "Default")
      (node (ref "K4") (pin "7") (pinfunction "7_7") (pintype "passive"))
    )
    (net (code "211") (name "unconnected-(K4-Pad8)") (class "Default")
      (node (ref "K4") (pin "8") (pinfunction "8_8") (pintype "passive"))
    )
    (net (code "212") (name "unconnected-(K4-Pad9)") (class "Default")
      (node (ref "K4") (pin "9") (pinfunction "9_9") (pintype "passive"))
    )
    (net (code "213") (name "unconnected-(K4-Pad10)") (class "Default")
      (node (ref "K4") (pin "10") (pinfunction "10_10") (pintype "passive"))
    )
    (net (code "214") (name "unconnected-(K5-Pad6)") (class "Default")
      (node (ref "K5") (pin "6") (pinfunction "6_6") (pintype "passive"))
    )
    (net (code "215") (name "unconnected-(U$2-PA12{slash}USB_DP{slash}CAN_TX-Pad33)") (class "Default")
      (node (ref "U$2") (pin "33") (pinfunction "PA12/USB_DP/CAN_TX_33") (pintype "bidirectional"))
    )
    (net (code "216") (name "unconnected-(U$2-PA15{slash}USART2_RX-Pad38)") (class "Default")
      (node (ref "U$2") (pin "38") (pinfunction "PA15/USART2_RX_38") (pintype "bidirectional"))
    )
    (net (code "217") (name "unconnected-(U$2-PB15{slash}WKUP7{slash}RTC_REFIN{slash}SPI2_MOSI-Pad28)") (class "Default")
      (node (ref "U$2") (pin "28") (pinfunction "PB15/WKUP7/RTC_REFIN/SPI2_MOSI_28") (pintype "bidirectional"))
    )
    (net (code "218") (name "unconnected-(U$2-PC13{slash}WKUP2{slash}RTC_TAMP1{slash}RTC_TS{slash}RTC_OUT-Pad2)") (class "Default")
      (node (ref "U$2") (pin "2") (pinfunction "PC13/WKUP2/RTC_TAMP1/RTC_TS/RTC_OUT_2") (pintype "bidirectional"))
    )
    (net (code "219") (name "unconnected-(U$2-PF0{slash}OSC_IN-Pad5)") (class "Default")
      (node (ref "U$2") (pin "5") (pinfunction "PF0/OSC_IN_5") (pintype "bidirectional"))
    )
    (net (code "220") (name "unconnected-(U$2-PF1{slash}OSC_OUT-Pad6)") (class "Default")
      (node (ref "U$2") (pin "6") (pinfunction "PF1/OSC_OUT_6") (pintype "bidirectional"))
    )
    (net (code "221") (name "unconnected-(U1-ON{slash}~{OFF}-Pad5)") (class "Default")
      (node (ref "U1") (pin "5") (pinfunction "ON/~{OFF}_5") (pintype "passive"))
    )
    (net (code "222") (name "unconnected-(U1-SS-Pad2)") (class "Default")
      (node (ref "U1") (pin "2") (pinfunction "SS_2") (pintype "passive"))
    )
    (net (code "223") (name "unconnected-(U1-SYNC-Pad3)") (class "Default")
      (node (ref "U1") (pin "3") (pinfunction "SYNC_3") (pintype "passive"))
    )
    (net (code "224") (name "unconnected-(U5-CLKOUT-Pad3)") (class "Default")
      (node (ref "U5") (pin "3") (pinfunction "CLKOUT_3") (pintype "passive"))
    )
    (net (code "225") (name "unconnected-(U5-NC-Pad5)") (class "Default")
      (node (ref "U5") (pin "5") (pinfunction "NC_5") (pintype "no_connect"))
    )
    (net (code "226") (name "unconnected-(X1-CR-Pad6)") (class "Default")
      (node (ref "X1") (pin "6") (pinfunction "CR_6") (pintype "input"))
    )
    (net (code "227") (name "unconnected-(X1-NC{slash}4-Pad4)") (class "Default")
      (node (ref "X1") (pin "4") (pinfunction "NC/4_4") (pintype "input"))
    )
    (net (code "228") (name "unconnected-(X1-NC{slash}5-Pad5)") (class "Default")
      (node (ref "X1") (pin "5") (pinfunction "NC/5_5") (pintype "input"))
    )
  )
)
